# ZYNQ_Motherboard_final.net
KiCad netlist of a schematic drawn in Altium Designer
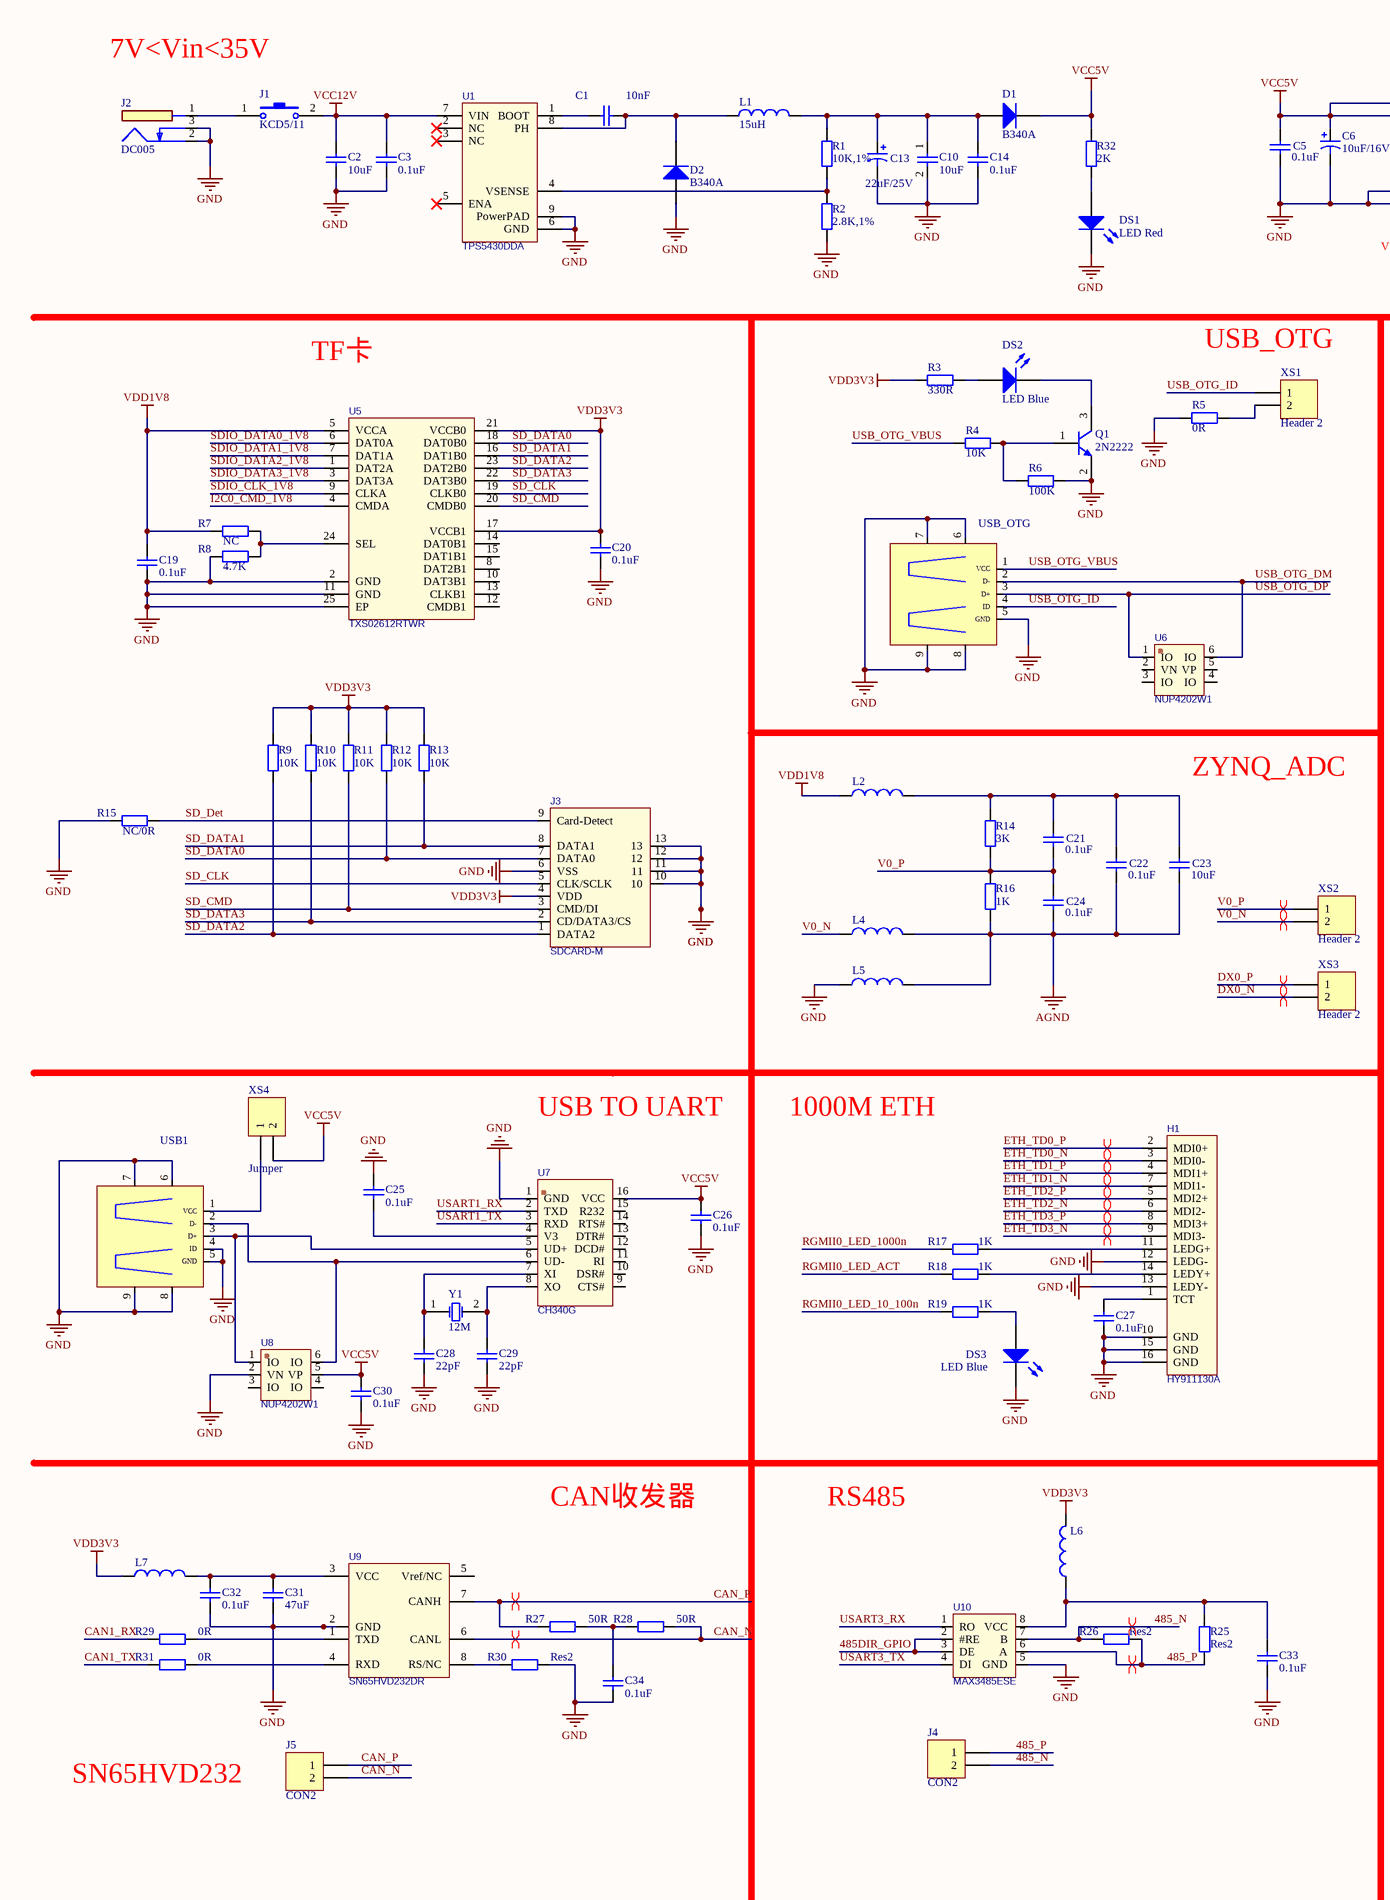
[diagram p0: ZYNQ_Motherboard_final.SchDoc, left]
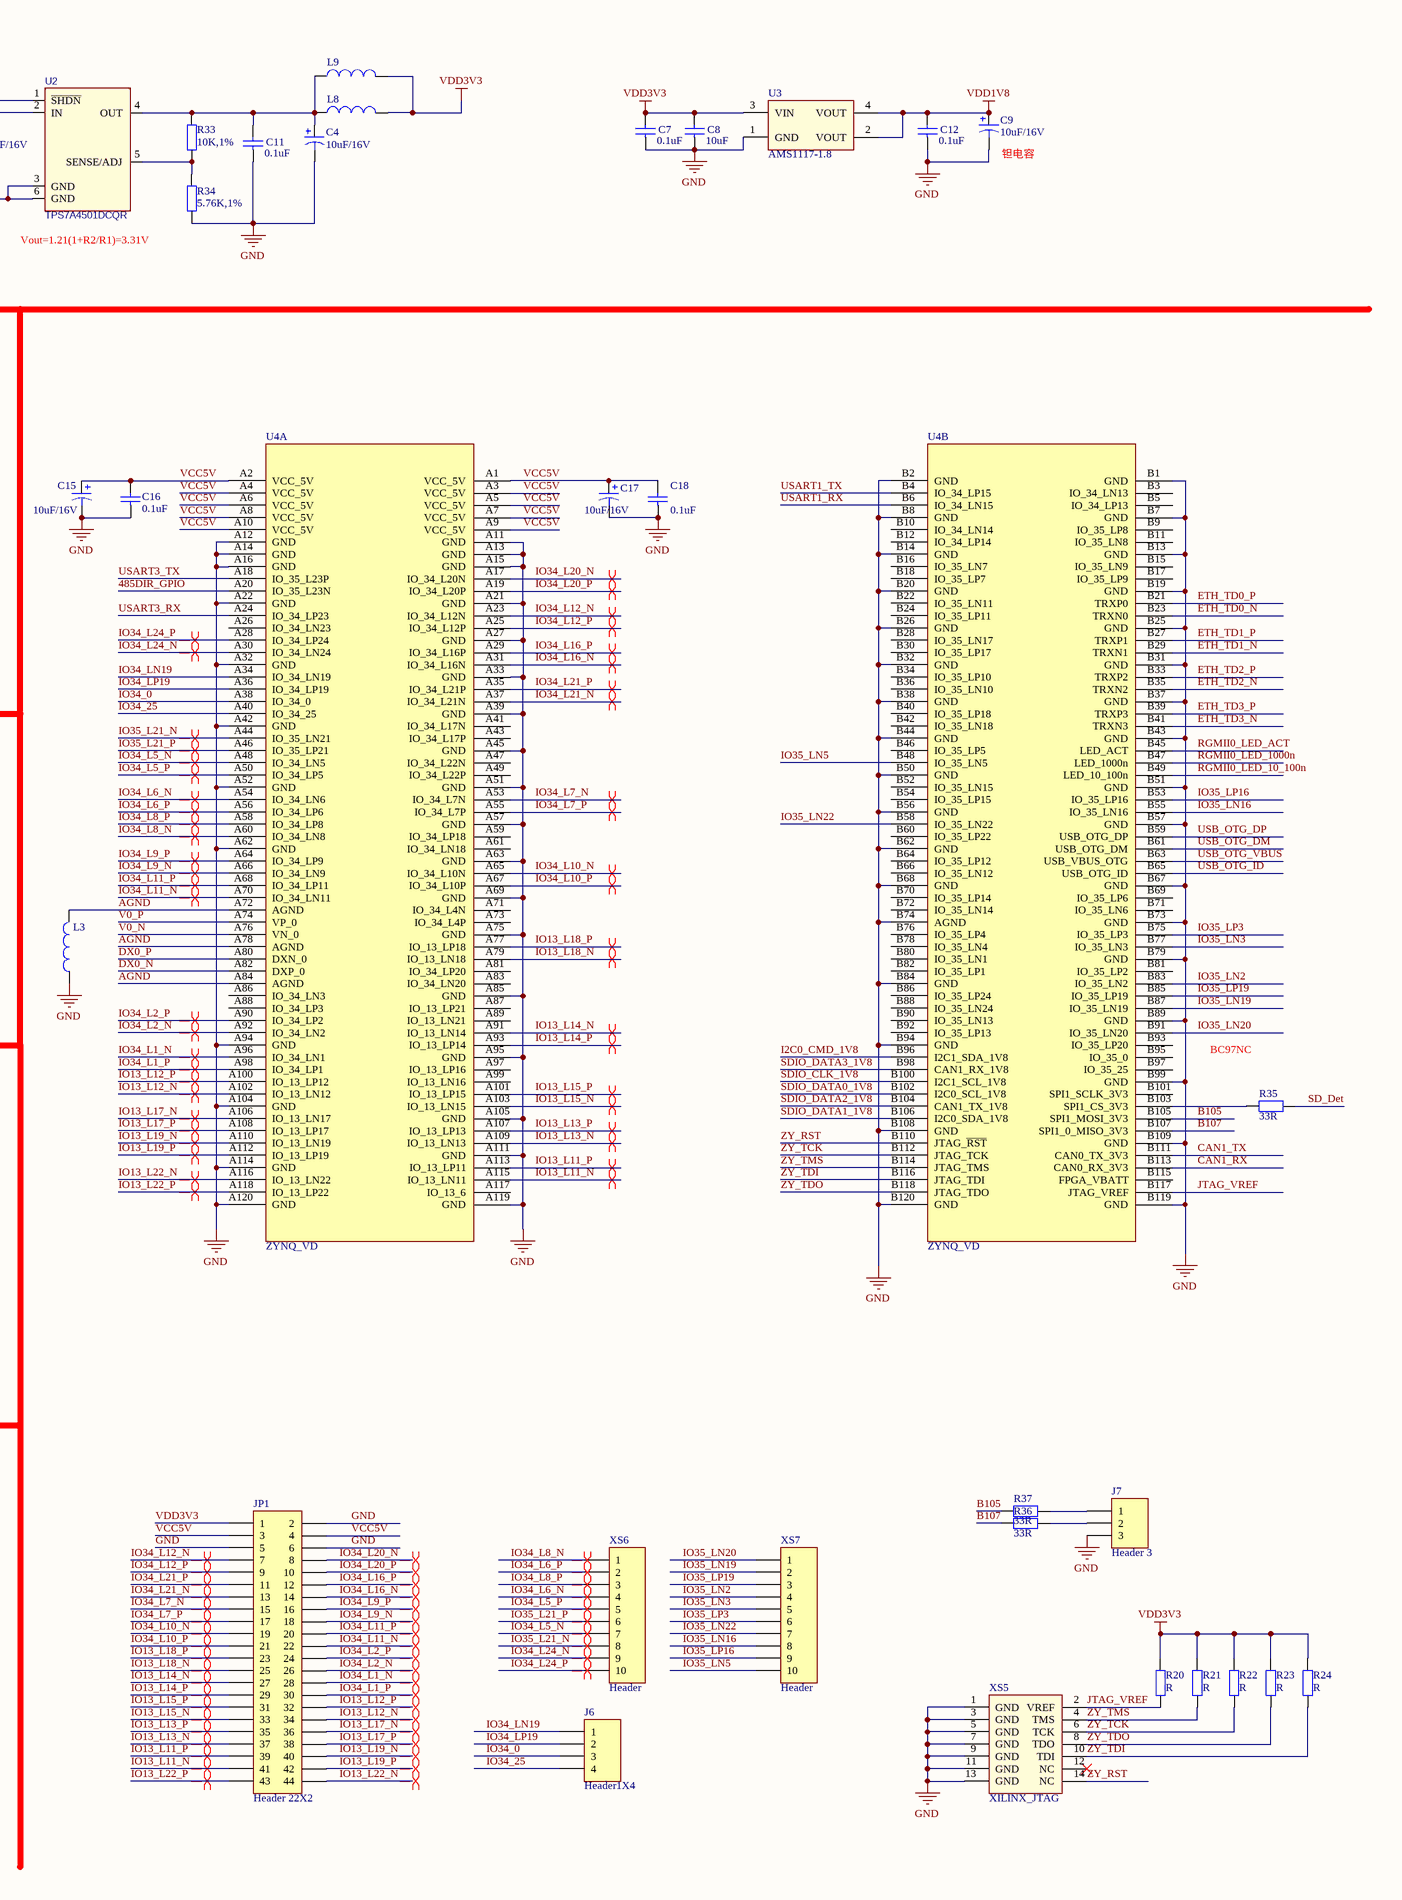
[diagram p1: ZYNQ_Motherboard_final.SchDoc, right]

(export (version "E")
  (design (tool "Eeschema 10.0.6"))
  (components
    (comp (ref "C1") (value "10nF") (footprint "0603") (libsource (lib "") (part "0603-CAP-50V 100±5%_1")))
    (comp (ref "C2") (value "10uF") (footprint "0805") (libsource (lib "") (part "0603-CAP-50V 100±5%_1")))
    (comp (ref "C3") (value "0.1uF") (footprint "0603") (libsource (lib "") (part "0603-CAP-50V 100±5%_1")))
    (comp (ref "C4")
      (value "10uF/16V")
      (footprint "shape_c")
      (description "Polarized Capacitor (Radial)")
      (fields (field (name "PUBLISHER") "Altium Limited"))
      (libsource (lib "") (part "Cap Pol1_1"))
    )
    (comp (ref "C5") (value "0.1uF") (footprint "0603") (libsource (lib "") (part "0603-CAP-50V 100±5%_1")))
    (comp (ref "C6")
      (value "10uF/16V")
      (footprint "shape_c")
      (description "Polarized Capacitor (Radial)")
      (fields (field (name "PUBLISHER") "Altium Limited"))
      (libsource (lib "") (part "Cap Pol1_1"))
    )
    (comp (ref "C7")
      (value "0.1uF")
      (footprint "0603")
      (libsource (lib "AJ-SCH_CAP") (part "0603-CAP-50V 100±5%"))
    )
    (comp (ref "C8")
      (value "10uF")
      (footprint "0805")
      (libsource (lib "AJ-SCH_CAP") (part "0603-CAP-50V 100±5%"))
    )
    (comp (ref "C9")
      (value "10uF/16V")
      (footprint "shape_c")
      (description "Polarized Capacitor (Radial)")
      (fields (field (name "PUBLISHER") "Altium Limited"))
      (libsource (lib "") (part "Cap Pol1_1"))
    )
    (comp (ref "C10") (value "10uF") (footprint "0805") (libsource (lib "") (part "0603-CAP-50V 100±5%_2")))
    (comp (ref "C11")
      (value "0.1uF")
      (footprint "0603")
      (libsource (lib "AJ-SCH_CAP") (part "0603-CAP-50V 100±5%"))
    )
    (comp (ref "C12")
      (value "0.1uF")
      (footprint "0603")
      (libsource (lib "AJ-SCH_CAP") (part "0603-CAP-50V 100±5%"))
    )
    (comp (ref "C13")
      (value "22uF/25V")
      (footprint "shape_c")
      (description "Polarized Capacitor (Radial)")
      (fields (field (name "PUBLISHER") "Altium Limited"))
      (libsource (lib "Miscellaneous Devices") (part "Cap Pol1"))
    )
    (comp (ref "C14") (value "0.1uF") (footprint "0603") (libsource (lib "") (part "0603-CAP-50V 100±5%_1")))
    (comp (ref "C15")
      (value "10uF/16V")
      (footprint "shape_c")
      (description "Polarized Capacitor (Radial)")
      (fields (field (name "PUBLISHER") "Altium Limited"))
      (libsource (lib "Miscellaneous Devices") (part "Cap Pol1"))
    )
    (comp (ref "C16") (value "0.1uF") (footprint "0603") (libsource (lib "") (part "0603-CAP-50V 100±5%_1")))
    (comp (ref "C17")
      (value "10uF/16V")
      (footprint "shape_c")
      (description "Polarized Capacitor (Radial)")
      (fields (field (name "PUBLISHER") "Altium Limited"))
      (libsource (lib "Miscellaneous Devices") (part "Cap Pol1"))
    )
    (comp (ref "C18") (value "0.1uF") (footprint "0603") (libsource (lib "") (part "0603-CAP-50V 100±5%_1")))
    (comp (ref "C19")
      (value "0.1uF")
      (footprint "0603")
      (libsource (lib "AJ-SCH_CAP") (part "0603-CAP-50V 100±5%"))
    )
    (comp (ref "C20")
      (value "0.1uF")
      (footprint "0603")
      (libsource (lib "AJ-SCH_CAP") (part "0603-CAP-50V 100±5%"))
    )
    (comp (ref "C21") (value "0.1uF") (footprint "0603") (libsource (lib "") (part "0603-CAP-50V 100±5%_1")))
    (comp (ref "C22") (value "0.1uF") (footprint "0603") (libsource (lib "") (part "0603-CAP-50V 100±5%_1")))
    (comp (ref "C23") (value "10uF") (footprint "0603") (libsource (lib "") (part "0603-CAP-50V 100±5%_1")))
    (comp (ref "C24") (value "0.1uF") (footprint "0603") (libsource (lib "") (part "0603-CAP-50V 100±5%_1")))
    (comp (ref "C25") (value "0.1uF") (footprint "0603") (libsource (lib "") (part "0603-CAP-50V 100±5%_1")))
    (comp (ref "C26")
      (value "0.1uF")
      (footprint "0603")
      (libsource (lib "AJ-SCH_CAP") (part "0603-CAP-50V 100±5%"))
    )
    (comp (ref "C27")
      (value "0.1uF")
      (footprint "0603")
      (libsource (lib "AJ-SCH_CAP") (part "0603-CAP-50V 100±5%"))
    )
    (comp (ref "C28") (value "22pF") (footprint "0603") (libsource (lib "") (part "0603-CAP-50V 100±5%_1")))
    (comp (ref "C29") (value "22pF") (footprint "0603") (libsource (lib "") (part "0603-CAP-50V 100±5%_1")))
    (comp (ref "C30") (value "0.1uF") (footprint "0603") (libsource (lib "") (part "0603-CAP-50V 100±5%_1")))
    (comp (ref "C31")
      (value "47uF")
      (footprint "0805")
      (libsource (lib "AJ-SCH_CAP") (part "0603-CAP-50V 100±5%"))
    )
    (comp (ref "C32")
      (value "0.1uF")
      (footprint "0603")
      (libsource (lib "AJ-SCH_CAP") (part "0603-CAP-50V 100±5%"))
    )
    (comp (ref "C33")
      (value "0.1uF")
      (footprint "0603")
      (libsource (lib "AJ-SCH_CAP") (part "0603-CAP-50V 100±5%"))
    )
    (comp (ref "C34")
      (value "0.1uF")
      (footprint "0603")
      (libsource (lib "AJ-SCH_CAP") (part "0603-CAP-50V 100±5%"))
    )
    (comp (ref "D1")
      (value "B340A")
      (footprint "SMA (DO-214AC)")
      (libsource (lib "AJ-SCH_Diode ") (part "SMD_整流二极管_FSL14"))
    )
    (comp (ref "D2")
      (value "B340A")
      (footprint "SMA (DO-214AC)")
      (libsource (lib "AJ-SCH_Diode ") (part "SMD_整流二极管_FSL14"))
    )
    (comp (ref "DS1")
      (value "LED Red")
      (footprint "SMDLED")
      (libsource (lib "AJ-SCH_Diode ") (part "0805_发光二极管_红色"))
    )
    (comp (ref "DS2")
      (value "LED Blue")
      (footprint "SMDLED")
      (libsource (lib "AJ-SCH_Diode ") (part "0805_发光二极管_红色"))
    )
    (comp (ref "DS3")
      (value "LED Blue")
      (footprint "SMDLED")
      (libsource (lib "AJ-SCH_Diode ") (part "0805_发光二极管_红色"))
    )
    (comp (ref "H1")
      (value "HY911130A")
      (footprint "RJ45_1000M")
      (fields (field (name "BOM_SUPPLIER PART") "C55679"))
      (libsource (lib "ZYNQ_Motherboard") (part "HY911130A"))
    )
    (comp (ref "J1")
      (value "KCD5/11")
      (footprint "KCD5/11")
      (description "Switch")
      (fields (field (name "PUBLISHER") "Altium Limited"))
      (libsource (lib "Miscellaneous Devices") (part "SW-PB"))
    )
    (comp (ref "J2")
      (value "DC005")
      (footprint "DC005")
      (description "Connector")
      (fields
        (field (name "MANUFACTURER_PART_NUMBER") "CON-SOCJ-2155")
        (field (name "MOUSER PART NUMBER") "992-CON-SOCJ-2155")
      )
      (libsource (lib "*") (part "CON-SOCJ-2155"))
    )
    (comp (ref "J3")
      (value "SDCARD-M")
      (footprint "SDCARD-M")
      (fields
        (field (name "BOM_SUPPLIER PART") "C202111")
        (field (name "BOM_MANUFACTURER PART") "DM3CS-SF")
        (field (name "CONTRIBUTOR") "LCSC")
      )
      (libsource (lib "ZYNQ_Motherboard") (part "DM3CS-SF"))
    )
    (comp (ref "J4")
      (value "CON2")
      (footprint "白色插座2")
      (description "Header, 2-Pin")
      (fields (field (name "PUBLISHER") "Altium Limited"))
      (libsource (lib "") (part "Header 2_2"))
    )
    (comp (ref "J5")
      (value "CON2")
      (footprint "白色插座2")
      (description "Header, 2-Pin")
      (fields (field (name "PUBLISHER") "Altium Limited"))
      (libsource (lib "") (part "Header 2_2"))
    )
    (comp (ref "J6")
      (value "Header1X4")
      (footprint "1X4_2.54")
      (description "Header, 4-Pin")
      (fields (field (name "PUBLISHER") "Altium Limited"))
      (libsource (lib "Miscellaneous Connectors") (part "Header 4"))
    )
    (comp (ref "J7")
      (value "Header 3")
      (footprint "HDR1X3")
      (description "Header, 3-Pin")
      (fields (field (name "PUBLISHER") "Altium Limited"))
      (libsource (lib "Miscellaneous Connectors") (part "Header 3"))
    )
    (comp (ref "JP1")
      (value "Header 22X2")
      (footprint "2x22_2.54")
      (description "Header, 22-Pin, Dual row")
      (fields (field (name "PUBLISHER") "Altium Limited"))
      (libsource (lib "Miscellaneous Connectors") (part "Header 22X2"))
    )
    (comp (ref "L1")
      (value "15uH")
      (footprint "L-SMD-12x12x10")
      (description "Inductor")
      (fields (field (name "PUBLISHER") "Altium Limited"))
      (libsource (lib "Miscellaneous Devices") (part "Inductor"))
    )
    (comp (ref "L2")
      (value "MPZ1608B471ATA00")
      (footprint "0603")
      (description "Inductor")
      (fields (field (name "PUBLISHER") "Altium Limited"))
      (libsource (lib "Miscellaneous Devices") (part "Inductor"))
    )
    (comp (ref "L3")
      (value "MPZ1608B471ATA00")
      (footprint "0603")
      (description "Inductor")
      (fields (field (name "PUBLISHER") "Altium Limited"))
      (libsource (lib "") (part "Inductor_1"))
    )
    (comp (ref "L4")
      (value "MPZ1608B471ATA00")
      (footprint "0603")
      (description "Inductor")
      (fields (field (name "PUBLISHER") "Altium Limited"))
      (libsource (lib "Miscellaneous Devices") (part "Inductor"))
    )
    (comp (ref "L5")
      (value "MPZ1608B471ATA00")
      (footprint "0603")
      (description "Inductor")
      (fields (field (name "PUBLISHER") "Altium Limited"))
      (libsource (lib "Miscellaneous Devices") (part "Inductor"))
    )
    (comp (ref "L6")
      (value "MPZ1608B471ATA00")
      (footprint "0603")
      (description "Inductor")
      (fields (field (name "PUBLISHER") "Altium Limited"))
      (libsource (lib "Miscellaneous Devices") (part "Inductor"))
    )
    (comp (ref "L7")
      (value "MPZ1608B471ATA00")
      (footprint "0603")
      (description "Inductor")
      (fields (field (name "PUBLISHER") "Altium Limited"))
      (libsource (lib "Miscellaneous Devices") (part "Inductor"))
    )
    (comp (ref "L8")
      (value "MPZ1608B471ATA00")
      (footprint "0603")
      (description "Inductor")
      (fields (field (name "PUBLISHER") "Altium Limited"))
      (libsource (lib "Miscellaneous Devices") (part "Inductor"))
    )
    (comp (ref "L9")
      (value "MPZ1608B471ATA00")
      (footprint "0603")
      (description "Inductor")
      (fields (field (name "PUBLISHER") "Altium Limited"))
      (libsource (lib "Miscellaneous Devices") (part "Inductor"))
    )
    (comp (ref "Q1")
      (value "2N2222")
      (footprint "SOT-23")
      (libsource (lib "AJ-SCH_Trans") (part "NPN_三极管_S9013 SOT-23"))
    )
    (comp (ref "R1")
      (value "10K,1%")
      (footprint "0603")
      (description "Resistor")
      (fields (field (name "PUBLISHER") "Altium Limited"))
      (libsource (lib "Miscellaneous Devices") (part "Res2"))
    )
    (comp (ref "R2")
      (value "2.8K,1%")
      (footprint "0603")
      (description "Resistor")
      (fields (field (name "PUBLISHER") "Altium Limited"))
      (libsource (lib "Miscellaneous Devices") (part "Res2"))
    )
    (comp (ref "R3")
      (value "330R")
      (footprint "0603")
      (description "Resistor")
      (fields (field (name "PUBLISHER") "Altium Limited"))
      (libsource (lib "") (part "Res2_1"))
    )
    (comp (ref "R4")
      (value "10K")
      (footprint "0603")
      (description "Resistor")
      (fields (field (name "PUBLISHER") "Altium Limited"))
      (libsource (lib "") (part "Res2_1"))
    )
    (comp (ref "R5")
      (value "0R")
      (footprint "0603")
      (description "Resistor")
      (fields (field (name "PUBLISHER") "Altium Limited"))
      (libsource (lib "") (part "Res2_1"))
    )
    (comp (ref "R6")
      (value "100K")
      (footprint "0603")
      (description "Resistor")
      (fields (field (name "PUBLISHER") "Altium Limited"))
      (libsource (lib "") (part "Res2_1"))
    )
    (comp (ref "R7")
      (value "NC")
      (footprint "0603")
      (description "Resistor")
      (fields (field (name "PUBLISHER") "Altium Limited"))
      (libsource (lib "") (part "Res2_1"))
    )
    (comp (ref "R8")
      (value "4.7K")
      (footprint "0603")
      (description "Resistor")
      (fields (field (name "PUBLISHER") "Altium Limited"))
      (libsource (lib "") (part "Res2_1"))
    )
    (comp (ref "R9")
      (value "10K")
      (footprint "0603")
      (description "Resistor")
      (fields (field (name "PUBLISHER") "Altium Limited"))
      (libsource (lib "") (part "Res2_3"))
    )
    (comp (ref "R10")
      (value "10K")
      (footprint "0603")
      (description "Resistor")
      (fields (field (name "PUBLISHER") "Altium Limited"))
      (libsource (lib "") (part "Res2_3"))
    )
    (comp (ref "R11")
      (value "10K")
      (footprint "0603")
      (description "Resistor")
      (fields (field (name "PUBLISHER") "Altium Limited"))
      (libsource (lib "") (part "Res2_3"))
    )
    (comp (ref "R12")
      (value "10K")
      (footprint "0603")
      (description "Resistor")
      (fields (field (name "PUBLISHER") "Altium Limited"))
      (libsource (lib "") (part "Res2_3"))
    )
    (comp (ref "R13")
      (value "10K")
      (footprint "0603")
      (description "Resistor")
      (fields (field (name "PUBLISHER") "Altium Limited"))
      (libsource (lib "") (part "Res2_3"))
    )
    (comp (ref "R14")
      (value "3K")
      (footprint "0603")
      (description "Resistor")
      (fields (field (name "PUBLISHER") "Altium Limited"))
      (libsource (lib "") (part "Res2_3"))
    )
    (comp (ref "R15")
      (value "NC/0R")
      (footprint "0603")
      (description "Resistor")
      (fields (field (name "PUBLISHER") "Altium Limited"))
      (libsource (lib "") (part "Res2_1"))
    )
    (comp (ref "R16")
      (value "1K")
      (footprint "0603")
      (description "Resistor")
      (fields (field (name "PUBLISHER") "Altium Limited"))
      (libsource (lib "") (part "Res2_3"))
    )
    (comp (ref "R17")
      (value "1K")
      (footprint "0603")
      (description "Resistor")
      (fields (field (name "PUBLISHER") "Altium Limited"))
      (libsource (lib "") (part "Res2_2"))
    )
    (comp (ref "R18")
      (value "1K")
      (footprint "0603")
      (description "Resistor")
      (fields (field (name "PUBLISHER") "Altium Limited"))
      (libsource (lib "") (part "Res2_2"))
    )
    (comp (ref "R19")
      (value "1K")
      (footprint "0603")
      (description "Resistor")
      (fields (field (name "PUBLISHER") "Altium Limited"))
      (libsource (lib "") (part "Res2_2"))
    )
    (comp (ref "R20")
      (value "R")
      (footprint "0603")
      (description "Resistor")
      (fields (field (name "PUBLISHER") "Altium Limited"))
      (libsource (lib "") (part "Res2_4"))
    )
    (comp (ref "R21")
      (value "R")
      (footprint "0603")
      (description "Resistor")
      (fields (field (name "PUBLISHER") "Altium Limited"))
      (libsource (lib "") (part "Res2_4"))
    )
    (comp (ref "R22")
      (value "R")
      (footprint "0603")
      (description "Resistor")
      (fields (field (name "PUBLISHER") "Altium Limited"))
      (libsource (lib "") (part "Res2_4"))
    )
    (comp (ref "R23")
      (value "R")
      (footprint "0603")
      (description "Resistor")
      (fields (field (name "PUBLISHER") "Altium Limited"))
      (libsource (lib "") (part "Res2_4"))
    )
    (comp (ref "R24")
      (value "R")
      (footprint "0603")
      (description "Resistor")
      (fields (field (name "PUBLISHER") "Altium Limited"))
      (libsource (lib "") (part "Res2_4"))
    )
    (comp (ref "R25")
      (value "Res2")
      (footprint "0603")
      (description "Resistor")
      (fields (field (name "PUBLISHER") "Altium Limited"))
      (libsource (lib "") (part "Res2_6"))
    )
    (comp (ref "R26")
      (value "Res2")
      (footprint "0603")
      (description "Resistor")
      (fields (field (name "PUBLISHER") "Altium Limited"))
      (libsource (lib "") (part "Res2_2"))
    )
    (comp (ref "R27")
      (value "50R")
      (footprint "0603")
      (description "Resistor")
      (fields (field (name "PUBLISHER") "Altium Limited"))
      (libsource (lib "") (part "Res2_2"))
    )
    (comp (ref "R28")
      (value "50R")
      (footprint "0603")
      (description "Resistor")
      (fields (field (name "PUBLISHER") "Altium Limited"))
      (libsource (lib "") (part "Res2_2"))
    )
    (comp (ref "R29")
      (value "0R")
      (footprint "0603")
      (description "Resistor")
      (fields (field (name "PUBLISHER") "Altium Limited"))
      (libsource (lib "") (part "Res2_2"))
    )
    (comp (ref "R30")
      (value "Res2")
      (footprint "0603")
      (description "Resistor")
      (fields (field (name "PUBLISHER") "Altium Limited"))
      (libsource (lib "") (part "Res2_7"))
    )
    (comp (ref "R31")
      (value "0R")
      (footprint "0603")
      (description "Resistor")
      (fields (field (name "PUBLISHER") "Altium Limited"))
      (libsource (lib "") (part "Res2_2"))
    )
    (comp (ref "R32")
      (value "2K")
      (footprint "0603")
      (description "Resistor")
      (fields (field (name "PUBLISHER") "Altium Limited"))
      (libsource (lib "Miscellaneous Devices") (part "Res2"))
    )
    (comp (ref "R33")
      (value "10K,1%")
      (footprint "0603")
      (description "Resistor")
      (fields (field (name "PUBLISHER") "Altium Limited"))
      (libsource (lib "Miscellaneous Devices") (part "Res2"))
    )
    (comp (ref "R34")
      (value "5.76K,1%")
      (footprint "0603")
      (description "Resistor")
      (fields (field (name "PUBLISHER") "Altium Limited"))
      (libsource (lib "Miscellaneous Devices") (part "Res2"))
    )
    (comp (ref "R35")
      (value "33R")
      (footprint "0603")
      (description "Resistor")
      (fields (field (name "PUBLISHER") "Altium Limited"))
      (libsource (lib "") (part "Res2_5"))
    )
    (comp (ref "R36")
      (value "33R")
      (footprint "0603")
      (description "Resistor")
      (fields (field (name "PUBLISHER") "Altium Limited"))
      (libsource (lib "") (part "Res2_2"))
    )
    (comp (ref "R37")
      (value "33R")
      (footprint "0603")
      (description "Resistor")
      (fields (field (name "PUBLISHER") "Altium Limited"))
      (libsource (lib "") (part "Res2_2"))
    )
    (comp (ref "U1")
      (value "TPS5430DDA")
      (footprint "SOIC8-PAD")
      (fields (field (name "BOM_MANUFACTURER PART") "TPS5430DDAR") (field (name "BOM_SUPPLIER PART") "C9864"))
      (libsource (lib "ZYNQ_Motherboard") (part "TPS5430DDAR"))
    )
    (comp (ref "U2")
      (value "TPS7A4501DCQR")
      (footprint "SOT223-6")
      (fields (field (name "BOM_SUPPLIER PART") "C840094") (field (name "CONTRIBUTOR") "LCSC"))
      (libsource (lib "ZYNQ_Motherboard") (part "TPS7A4501DCQR"))
    )
    (comp (ref "U3")
      (value "AMS1117-1.8")
      (footprint "SOT-223")
      (libsource (lib "ZYNQ_Motherboard") (part "AMS1117-1.8"))
    )
    (comp (ref "U4")
      (value "ZYNQ_VD")
      (footprint "ZYNQ_VD")
      (libsource (lib "ZYNQ_Motherboard") (part "ZYNQ"))
    )
    (comp (ref "U5")
      (value "TXS02612RTWR")
      (footprint "WQFN24_PAD")
      (fields (field (name "BOM_SUPPLIER PART") "C140276") (field (name "CONTRIBUTOR") "LCSC"))
      (libsource (lib "ZYNQ_Motherboard") (part "TXS02612RTWR"))
    )
    (comp (ref "U6")
      (value "NUP4202W1")
      (footprint "SOT-363")
      (fields
        (field (name "BOM_MANUFACTURER PART") "NUP4202W1T2G")
        (field (name "BOM_SUPPLIER PART") "C89319")
      )
      (libsource (lib "ZYNQ_Motherboard") (part "NUP4202W1T2G"))
    )
    (comp (ref "U7")
      (value "CH340G")
      (footprint "SOP16M")
      (fields (field (name "BOM_SUPPLIER PART") "C14267"))
      (libsource (lib "ZYNQ_Motherboard") (part "CH340G"))
    )
    (comp (ref "U8")
      (value "NUP4202W1")
      (footprint "SOT-363")
      (fields
        (field (name "BOM_MANUFACTURER PART") "NUP4202W1T2G")
        (field (name "BOM_SUPPLIER PART") "C89319")
      )
      (libsource (lib "ZYNQ_Motherboard") (part "NUP4202W1T2G"))
    )
    (comp (ref "U9")
      (value "SN65HVD232DR")
      (footprint "SOIC8")
      (fields (field (name "BOM_SUPPLIER PART") "C30530"))
      (libsource (lib "ZYNQ_Motherboard") (part "SN65HVD232DR"))
    )
    (comp (ref "U10")
      (value "MAX3485ESE")
      (footprint "SOP8")
      (fields
        (field (name "BOM_SUPPLIER PART") "C668204")
        (field (name "BOM_MANUFACTURER PART") "MAX3485ESA")
        (field (name "CONTRIBUTOR") "LCSC")
      )
      (libsource (lib "ZYNQ_Motherboard") (part "MAX3485ESE"))
    )
    (comp (ref "USB1")
      (value "USB")
      (footprint "USB/SM0.8-6H5")
      (libsource (lib "ZYNQ_Motherboard") (part "USB-micro"))
    )
    (comp (ref "USB_OTG")
      (value "USB")
      (footprint "USB/SM0.8-6H5")
      (libsource (lib "ZYNQ_Motherboard") (part "USB-micro"))
    )
    (comp (ref "XS1")
      (value "Header 2")
      (footprint "1X2_2.54")
      (description "Header, 2-Pin")
      (fields (field (name "PUBLISHER") "Altium Limited"))
      (libsource (lib "") (part "Header 2_1"))
    )
    (comp (ref "XS2")
      (value "Header 2")
      (footprint "1X2_2.54")
      (description "Header, 2-Pin")
      (fields (field (name "PUBLISHER") "Altium Limited"))
      (libsource (lib "") (part "Header 2_1"))
    )
    (comp (ref "XS3")
      (value "Header 2")
      (footprint "1X2_2.54")
      (description "Header, 2-Pin")
      (fields (field (name "PUBLISHER") "Altium Limited"))
      (libsource (lib "") (part "Header 2_1"))
    )
    (comp (ref "XS4")
      (value "Jumper")
      (footprint "1X2_2.54")
      (description "Header, 2-Pin")
      (fields (field (name "PUBLISHER") "Altium Limited"))
      (libsource (lib "Miscellaneous Connectors") (part "Header 2"))
    )
    (comp (ref "XS5")
      (value "XILINX_JTAG")
      (footprint "JTAG14-2.0")
      (libsource (lib "ZYNQ_Motherboard") (part "XILINX_JTAG"))
    )
    (comp (ref "XS6")
      (value "Header")
      (footprint "JTAG_10")
      (description "Header, 10-Pin")
      (fields (field (name "PUBLISHER") "Altium Limited"))
      (libsource (lib "Miscellaneous Connectors") (part "Header 10"))
    )
    (comp (ref "XS7")
      (value "Header")
      (footprint "1x9_2.0")
      (description "Header, 10-Pin")
      (fields (field (name "PUBLISHER") "Altium Limited"))
      (libsource (lib "Miscellaneous Connectors") (part "Header 10"))
    )
    (comp (ref "Y1") (value "12M") (footprint "晶振") (libsource (lib "AJ-SCH_SW") (part "晶振(DIP 3)_4MHz")))
  )
  (nets
    (net (code "1") (name "/485DIR_GPIO") (class "Default")
      (node (ref "U10") (pin "2") (pinfunction "#RE_2") (pintype "passive"))
      (node (ref "U10") (pin "3") (pinfunction "DE_3") (pintype "passive"))
      (node (ref "U4") (pin "A20") (pinfunction "IO_35_L23N_A20") (pintype "passive"))
    )
    (net (code "2") (name "/485_N") (class "Default")
      (node (ref "J4") (pin "2") (pinfunction "2_2") (pintype "passive"))
      (node (ref "R26") (pin "1") (pinfunction "1_1") (pintype "passive"))
      (node (ref "U10") (pin "7") (pinfunction "B_7") (pintype "passive"))
    )
    (net (code "3") (name "/485_P") (class "Default")
      (node (ref "J4") (pin "1") (pinfunction "1_1") (pintype "passive"))
      (node (ref "R25") (pin "1") (pinfunction "1_1") (pintype "passive"))
      (node (ref "R26") (pin "2") (pinfunction "2_2") (pintype "passive"))
      (node (ref "U10") (pin "6") (pinfunction "A_6") (pintype "passive"))
    )
    (net (code "4") (name "/B105") (class "Default")
      (node (ref "R37") (pin "1") (pinfunction "1_1") (pintype "passive"))
      (node (ref "U4") (pin "B105") (pinfunction "SPI1_MOSI_3V3_B105") (pintype "passive"))
    )
    (net (code "5") (name "/B107") (class "Default")
      (node (ref "R36") (pin "1") (pinfunction "1_1") (pintype "passive"))
      (node (ref "U4") (pin "B107") (pinfunction "SPI1_0_MISO_3V3_B107") (pintype "passive"))
    )
    (net (code "6") (name "/CAN1_RX") (class "Default")
      (node (ref "R29") (pin "1") (pinfunction "1_1") (pintype "passive"))
      (node (ref "U4") (pin "B113") (pinfunction "CAN0_RX_3V3_B113") (pintype "passive"))
    )
    (net (code "7") (name "/CAN1_TX") (class "Default")
      (node (ref "R31") (pin "1") (pinfunction "1_1") (pintype "passive"))
      (node (ref "U4") (pin "B111") (pinfunction "CAN0_TX_3V3_B111") (pintype "passive"))
    )
    (net (code "8") (name "/CAN_N") (class "Default")
      (node (ref "J5") (pin "2") (pinfunction "2_2") (pintype "passive"))
      (node (ref "R28") (pin "2") (pinfunction "2_2") (pintype "passive"))
      (node (ref "U9") (pin "6") (pinfunction "CANL_6") (pintype "passive"))
    )
    (net (code "9") (name "/CAN_P") (class "Default")
      (node (ref "J5") (pin "1") (pinfunction "1_1") (pintype "passive"))
      (node (ref "R27") (pin "1") (pinfunction "1_1") (pintype "passive"))
      (node (ref "U9") (pin "7") (pinfunction "CANH_7") (pintype "passive"))
    )
    (net (code "10") (name "/DX0_N") (class "Default")
      (node (ref "U4") (pin "A82") (pinfunction "DXP_0_A82") (pintype "passive"))
      (node (ref "XS3") (pin "2") (pinfunction "2_2") (pintype "passive"))
    )
    (net (code "11") (name "/DX0_P") (class "Default")
      (node (ref "U4") (pin "A80") (pinfunction "DXN_0_A80") (pintype "passive"))
      (node (ref "XS3") (pin "1") (pinfunction "1_1") (pintype "passive"))
    )
    (net (code "12") (name "/ETH_TD0_N") (class "Default")
      (node (ref "H1") (pin "3") (pinfunction "MDI0-_3") (pintype "passive"))
      (node (ref "U4") (pin "B23") (pinfunction "TRXN0_B23") (pintype "passive"))
    )
    (net (code "13") (name "/ETH_TD0_P") (class "Default")
      (node (ref "H1") (pin "2") (pinfunction "MDI0+_2") (pintype "passive"))
      (node (ref "U4") (pin "B21") (pinfunction "TRXP0_B21") (pintype "passive"))
    )
    (net (code "14") (name "/ETH_TD1_N") (class "Default")
      (node (ref "H1") (pin "7") (pinfunction "MDI1-_7") (pintype "passive"))
      (node (ref "U4") (pin "B29") (pinfunction "TRXN1_B29") (pintype "passive"))
    )
    (net (code "15") (name "/ETH_TD1_P") (class "Default")
      (node (ref "H1") (pin "4") (pinfunction "MDI1+_4") (pintype "passive"))
      (node (ref "U4") (pin "B27") (pinfunction "TRXP1_B27") (pintype "passive"))
    )
    (net (code "16") (name "/ETH_TD2_N") (class "Default")
      (node (ref "H1") (pin "6") (pinfunction "MDI2-_6") (pintype "passive"))
      (node (ref "U4") (pin "B35") (pinfunction "TRXN2_B35") (pintype "passive"))
    )
    (net (code "17") (name "/ETH_TD2_P") (class "Default")
      (node (ref "H1") (pin "5") (pinfunction "MDI2+_5") (pintype "passive"))
      (node (ref "U4") (pin "B33") (pinfunction "TRXP2_B33") (pintype "passive"))
    )
    (net (code "18") (name "/ETH_TD3_N") (class "Default")
      (node (ref "H1") (pin "9") (pinfunction "MDI3-_9") (pintype "passive"))
      (node (ref "U4") (pin "B41") (pinfunction "TRXN3_B41") (pintype "passive"))
    )
    (net (code "19") (name "/ETH_TD3_P") (class "Default")
      (node (ref "H1") (pin "8") (pinfunction "MDI3+_8") (pintype "passive"))
      (node (ref "U4") (pin "B39") (pinfunction "TRXP3_B39") (pintype "passive"))
    )
    (net (code "20") (name "/I2C0_CMD_1V8") (class "Default")
      (node (ref "U4") (pin "B96") (pinfunction "I2C1_SDA_1V8_B96") (pintype "passive"))
      (node (ref "U5") (pin "4") (pinfunction "CMDA_4") (pintype "passive"))
    )
    (net (code "21") (name "/IO13_L11_N") (class "Default")
      (node (ref "JP1") (pin "41") (pinfunction "41_41") (pintype "passive"))
      (node (ref "U4") (pin "A115") (pinfunction "IO_13_LN11_A115") (pintype "passive"))
    )
    (net (code "22") (name "/IO13_L11_P") (class "Default")
      (node (ref "JP1") (pin "39") (pinfunction "39_39") (pintype "passive"))
      (node (ref "U4") (pin "A113") (pinfunction "IO_13_LP11_A113") (pintype "passive"))
    )
    (net (code "23") (name "/IO13_L12_N") (class "Default")
      (node (ref "JP1") (pin "34") (pinfunction "34_34") (pintype "passive"))
      (node (ref "U4") (pin "A102") (pinfunction "IO_13_LN12_A102") (pintype "passive"))
    )
    (net (code "24") (name "/IO13_L12_P") (class "Default")
      (node (ref "JP1") (pin "32") (pinfunction "32_32") (pintype "passive"))
      (node (ref "U4") (pin "A100") (pinfunction "IO_13_LP12_A100") (pintype "passive"))
    )
    (net (code "25") (name "/IO13_L13_N") (class "Default")
      (node (ref "JP1") (pin "37") (pinfunction "37_37") (pintype "passive"))
      (node (ref "U4") (pin "A109") (pinfunction "IO_13_LN13_A109") (pintype "passive"))
    )
    (net (code "26") (name "/IO13_L13_P") (class "Default")
      (node (ref "JP1") (pin "35") (pinfunction "35_35") (pintype "passive"))
      (node (ref "U4") (pin "A107") (pinfunction "IO_13_LP13_A107") (pintype "passive"))
    )
    (net (code "27") (name "/IO13_L14_N") (class "Default")
      (node (ref "JP1") (pin "27") (pinfunction "27_27") (pintype "passive"))
      (node (ref "U4") (pin "A91") (pinfunction "IO_13_LN14_A91") (pintype "passive"))
    )
    (net (code "28") (name "/IO13_L14_P") (class "Default")
      (node (ref "JP1") (pin "29") (pinfunction "29_29") (pintype "passive"))
      (node (ref "U4") (pin "A93") (pinfunction "IO_13_LP14_A93") (pintype "passive"))
    )
    (net (code "29") (name "/IO13_L15_N") (class "Default")
      (node (ref "JP1") (pin "33") (pinfunction "33_33") (pintype "passive"))
      (node (ref "U4") (pin "A103") (pinfunction "IO_13_LN15_A103") (pintype "passive"))
    )
    (net (code "30") (name "/IO13_L15_P") (class "Default")
      (node (ref "JP1") (pin "31") (pinfunction "31_31") (pintype "passive"))
      (node (ref "U4") (pin "A101") (pinfunction "IO_13_LP15_A101") (pintype "passive"))
    )
    (net (code "31") (name "/IO13_L17_N") (class "Default")
      (node (ref "JP1") (pin "36") (pinfunction "36_36") (pintype "passive"))
      (node (ref "U4") (pin "A106") (pinfunction "IO_13_LN17_A106") (pintype "passive"))
    )
    (net (code "32") (name "/IO13_L17_P") (class "Default")
      (node (ref "JP1") (pin "38") (pinfunction "38_38") (pintype "passive"))
      (node (ref "U4") (pin "A108") (pinfunction "IO_13_LP17_A108") (pintype "passive"))
    )
    (net (code "33") (name "/IO13_L18_N") (class "Default")
      (node (ref "JP1") (pin "25") (pinfunction "25_25") (pintype "passive"))
      (node (ref "U4") (pin "A79") (pinfunction "IO_13_LN18_A79") (pintype "passive"))
    )
    (net (code "34") (name "/IO13_L18_P") (class "Default")
      (node (ref "JP1") (pin "23") (pinfunction "23_23") (pintype "passive"))
      (node (ref "U4") (pin "A77") (pinfunction "IO_13_LP18_A77") (pintype "passive"))
    )
    (net (code "35") (name "/IO13_L19_N") (class "Default")
      (node (ref "JP1") (pin "40") (pinfunction "40_40") (pintype "passive"))
      (node (ref "U4") (pin "A110") (pinfunction "IO_13_LN19_A110") (pintype "passive"))
    )
    (net (code "36") (name "/IO13_L19_P") (class "Default")
      (node (ref "JP1") (pin "42") (pinfunction "42_42") (pintype "passive"))
      (node (ref "U4") (pin "A112") (pinfunction "IO_13_LP19_A112") (pintype "passive"))
    )
    (net (code "37") (name "/IO13_L22_N") (class "Default")
      (node (ref "JP1") (pin "44") (pinfunction "44_44") (pintype "passive"))
      (node (ref "U4") (pin "A116") (pinfunction "IO_13_LN22_A116") (pintype "passive"))
    )
    (net (code "38") (name "/IO13_L22_P") (class "Default")
      (node (ref "JP1") (pin "43") (pinfunction "43_43") (pintype "passive"))
      (node (ref "U4") (pin "A118") (pinfunction "IO_13_LP22_A118") (pintype "passive"))
    )
    (net (code "39") (name "/IO34_0") (class "Default")
      (node (ref "J6") (pin "3") (pinfunction "3_3") (pintype "passive"))
      (node (ref "U4") (pin "A38") (pinfunction "IO_34_0_A38") (pintype "passive"))
    )
    (net (code "40") (name "/IO34_25") (class "Default")
      (node (ref "J6") (pin "4") (pinfunction "4_4") (pintype "passive"))
      (node (ref "U4") (pin "A40") (pinfunction "IO_34_25_A40") (pintype "passive"))
    )
    (net (code "41") (name "/IO34_L1_N") (class "Default")
      (node (ref "JP1") (pin "28") (pinfunction "28_28") (pintype "passive"))
      (node (ref "U4") (pin "A96") (pinfunction "IO_34_LN1_A96") (pintype "passive"))
    )
    (net (code "42") (name "/IO34_L1_P") (class "Default")
      (node (ref "JP1") (pin "30") (pinfunction "30_30") (pintype "passive"))
      (node (ref "U4") (pin "A98") (pinfunction "IO_34_LP1_A98") (pintype "passive"))
    )
    (net (code "43") (name "/IO34_L2_N") (class "Default")
      (node (ref "JP1") (pin "26") (pinfunction "26_26") (pintype "passive"))
      (node (ref "U4") (pin "A92") (pinfunction "IO_34_LN2_A92") (pintype "passive"))
    )
    (net (code "44") (name "/IO34_L2_P") (class "Default")
      (node (ref "JP1") (pin "24") (pinfunction "24_24") (pintype "passive"))
      (node (ref "U4") (pin "A90") (pinfunction "IO_34_LP2_A90") (pintype "passive"))
    )
    (net (code "45") (name "/IO34_L5_N") (class "Default")
      (node (ref "U4") (pin "A48") (pinfunction "IO_34_LN5_A48") (pintype "passive"))
      (node (ref "XS6") (pin "7") (pinfunction "7_7") (pintype "passive"))
    )
    (net (code "46") (name "/IO34_L5_P") (class "Default")
      (node (ref "U4") (pin "A50") (pinfunction "IO_34_LP5_A50") (pintype "passive"))
      (node (ref "XS6") (pin "5") (pinfunction "5_5") (pintype "passive"))
    )
    (net (code "47") (name "/IO34_L6_N") (class "Default")
      (node (ref "U4") (pin "A54") (pinfunction "IO_34_LN6_A54") (pintype "passive"))
      (node (ref "XS6") (pin "4") (pinfunction "4_4") (pintype "passive"))
    )
    (net (code "48") (name "/IO34_L6_P") (class "Default")
      (node (ref "U4") (pin "A56") (pinfunction "IO_34_LP6_A56") (pintype "passive"))
      (node (ref "XS6") (pin "2") (pinfunction "2_2") (pintype "passive"))
    )
    (net (code "49") (name "/IO34_L7_N") (class "Default")
      (node (ref "JP1") (pin "15") (pinfunction "15_15") (pintype "passive"))
      (node (ref "U4") (pin "A53") (pinfunction "IO_34_L7N_A53") (pintype "passive"))
    )
    (net (code "50") (name "/IO34_L7_P") (class "Default")
      (node (ref "JP1") (pin "17") (pinfunction "17_17") (pintype "passive"))
      (node (ref "U4") (pin "A55") (pinfunction "IO_34_L7P_A55") (pintype "passive"))
    )
    (net (code "51") (name "/IO34_L8_N") (class "Default")
      (node (ref "U4") (pin "A60") (pinfunction "IO_34_LN8_A60") (pintype "passive"))
      (node (ref "XS6") (pin "1") (pinfunction "1_1") (pintype "passive"))
    )
    (net (code "52") (name "/IO34_L8_P") (class "Default")
      (node (ref "U4") (pin "A58") (pinfunction "IO_34_LP8_A58") (pintype "passive"))
      (node (ref "XS6") (pin "3") (pinfunction "3_3") (pintype "passive"))
    )
    (net (code "53") (name "/IO34_L9_N") (class "Default")
      (node (ref "JP1") (pin "18") (pinfunction "18_18") (pintype "passive"))
      (node (ref "U4") (pin "A66") (pinfunction "IO_34_LN9_A66") (pintype "passive"))
    )
    (net (code "54") (name "/IO34_L9_P") (class "Default")
      (node (ref "JP1") (pin "16") (pinfunction "16_16") (pintype "passive"))
      (node (ref "U4") (pin "A64") (pinfunction "IO_34_LP9_A64") (pintype "passive"))
    )
    (net (code "55") (name "/IO34_L10_N") (class "Default")
      (node (ref "JP1") (pin "19") (pinfunction "19_19") (pintype "passive"))
      (node (ref "U4") (pin "A65") (pinfunction "IO_34_L10N_A65") (pintype "passive"))
    )
    (net (code "56") (name "/IO34_L10_P") (class "Default")
      (node (ref "JP1") (pin "21") (pinfunction "21_21") (pintype "passive"))
      (node (ref "U4") (pin "A67") (pinfunction "IO_34_L10P_A67") (pintype "passive"))
    )
    (net (code "57") (name "/IO34_L11_N") (class "Default")
      (node (ref "JP1") (pin "22") (pinfunction "22_22") (pintype "passive"))
      (node (ref "U4") (pin "A70") (pinfunction "IO_34_LN11_A70") (pintype "passive"))
    )
    (net (code "58") (name "/IO34_L11_P") (class "Default")
      (node (ref "JP1") (pin "20") (pinfunction "20_20") (pintype "passive"))
      (node (ref "U4") (pin "A68") (pinfunction "IO_34_LP11_A68") (pintype "passive"))
    )
    (net (code "59") (name "/IO34_L12_N") (class "Default")
      (node (ref "JP1") (pin "7") (pinfunction "7_7") (pintype "passive"))
      (node (ref "U4") (pin "A23") (pinfunction "IO_34_L12N_A23") (pintype "passive"))
    )
    (net (code "60") (name "/IO34_L12_P") (class "Default")
      (node (ref "JP1") (pin "9") (pinfunction "9_9") (pintype "passive"))
      (node (ref "U4") (pin "A25") (pinfunction "IO_34_L12P_A25") (pintype "passive"))
    )
    (net (code "61") (name "/IO34_L16_N") (class "Default")
      (node (ref "JP1") (pin "14") (pinfunction "14_14") (pintype "passive"))
      (node (ref "U4") (pin "A31") (pinfunction "IO_34_L16N_A31") (pintype "passive"))
    )
    (net (code "62") (name "/IO34_L16_P") (class "Default")
      (node (ref "JP1") (pin "12") (pinfunction "12_12") (pintype "passive"))
      (node (ref "U4") (pin "A29") (pinfunction "IO_34_L16P_A29") (pintype "passive"))
    )
    (net (code "63") (name "/IO34_L20_N") (class "Default")
      (node (ref "JP1") (pin "8") (pinfunction "8_8") (pintype "passive"))
      (node (ref "U4") (pin "A17") (pinfunction "IO_34_L20N_A17") (pintype "passive"))
    )
    (net (code "64") (name "/IO34_L20_P") (class "Default")
      (node (ref "JP1") (pin "10") (pinfunction "10_10") (pintype "passive"))
      (node (ref "U4") (pin "A19") (pinfunction "IO_34_L20P_A19") (pintype "passive"))
    )
    (net (code "65") (name "/IO34_L21_N") (class "Default")
      (node (ref "JP1") (pin "13") (pinfunction "13_13") (pintype "passive"))
      (node (ref "U4") (pin "A37") (pinfunction "IO_34_L21N_A37") (pintype "passive"))
    )
    (net (code "66") (name "/IO34_L21_P") (class "Default")
      (node (ref "JP1") (pin "11") (pinfunction "11_11") (pintype "passive"))
      (node (ref "U4") (pin "A35") (pinfunction "IO_34_L21P_A35") (pintype "passive"))
    )
    (net (code "67") (name "/IO34_L24_N") (class "Default")
      (node (ref "U4") (pin "A30") (pinfunction "IO_34_LN24_A30") (pintype "passive"))
      (node (ref "XS6") (pin "9") (pinfunction "9_9") (pintype "passive"))
    )
    (net (code "68") (name "/IO34_L24_P") (class "Default")
      (node (ref "U4") (pin "A28") (pinfunction "IO_34_LP24_A28") (pintype "passive"))
      (node (ref "XS6") (pin "10") (pinfunction "10_10") (pintype "passive"))
    )
    (net (code "69") (name "/IO34_LN19") (class "Default")
      (node (ref "J6") (pin "1") (pinfunction "1_1") (pintype "passive"))
      (node (ref "U4") (pin "A34") (pinfunction "IO_34_LN19_A34") (pintype "passive"))
    )
    (net (code "70") (name "/IO34_LP19") (class "Default")
      (node (ref "J6") (pin "2") (pinfunction "2_2") (pintype "passive"))
      (node (ref "U4") (pin "A36") (pinfunction "IO_34_LP19_A36") (pintype "passive"))
    )
    (net (code "71") (name "/IO35_L21_N") (class "Default")
      (node (ref "U4") (pin "A44") (pinfunction "IO_35_LN21_A44") (pintype "passive"))
      (node (ref "XS6") (pin "8") (pinfunction "8_8") (pintype "passive"))
    )
    (net (code "72") (name "/IO35_L21_P") (class "Default")
      (node (ref "U4") (pin "A46") (pinfunction "IO_35_LP21_A46") (pintype "passive"))
      (node (ref "XS6") (pin "6") (pinfunction "6_6") (pintype "passive"))
    )
    (net (code "73") (name "/IO35_LN2") (class "Default")
      (node (ref "U4") (pin "B83") (pinfunction "IO_35_LN2_B83") (pintype "passive"))
      (node (ref "XS7") (pin "4") (pinfunction "4_4") (pintype "passive"))
    )
    (net (code "74") (name "/IO35_LN3") (class "Default")
      (node (ref "U4") (pin "B77") (pinfunction "IO_35_LN3_B77") (pintype "passive"))
      (node (ref "XS7") (pin "5") (pinfunction "5_5") (pintype "passive"))
    )
    (net (code "75") (name "/IO35_LN5") (class "Default")
      (node (ref "U4") (pin "B48") (pinfunction "IO_35_LN5_B48") (pintype "passive"))
      (node (ref "XS7") (pin "10") (pinfunction "10_10") (pintype "passive"))
    )
    (net (code "76") (name "/IO35_LN16") (class "Default")
      (node (ref "U4") (pin "B55") (pinfunction "IO_35_LN16_B55") (pintype "passive"))
      (node (ref "XS7") (pin "8") (pinfunction "8_8") (pintype "passive"))
    )
    (net (code "77") (name "/IO35_LN19") (class "Default")
      (node (ref "U4") (pin "B87") (pinfunction "IO_35_LN19_B87") (pintype "passive"))
      (node (ref "XS7") (pin "2") (pinfunction "2_2") (pintype "passive"))
    )
    (net (code "78") (name "/IO35_LN20") (class "Default")
      (node (ref "U4") (pin "B91") (pinfunction "IO_35_LN20_B91") (pintype "passive"))
      (node (ref "XS7") (pin "1") (pinfunction "1_1") (pintype "passive"))
    )
    (net (code "79") (name "/IO35_LN22") (class "Default")
      (node (ref "U4") (pin "B58") (pinfunction "IO_35_LN22_B58") (pintype "passive"))
      (node (ref "XS7") (pin "7") (pinfunction "7_7") (pintype "passive"))
    )
    (net (code "80") (name "/IO35_LP3") (class "Default")
      (node (ref "U4") (pin "B75") (pinfunction "IO_35_LP3_B75") (pintype "passive"))
      (node (ref "XS7") (pin "6") (pinfunction "6_6") (pintype "passive"))
    )
    (net (code "81") (name "/IO35_LP16") (class "Default")
      (node (ref "U4") (pin "B53") (pinfunction "IO_35_LP16_B53") (pintype "passive"))
      (node (ref "XS7") (pin "9") (pinfunction "9_9") (pintype "passive"))
    )
    (net (code "82") (name "/IO35_LP19") (class "Default")
      (node (ref "U4") (pin "B85") (pinfunction "IO_35_LP19_B85") (pintype "passive"))
      (node (ref "XS7") (pin "3") (pinfunction "3_3") (pintype "passive"))
    )
    (net (code "83") (name "/JTAG_VREF") (class "Default")
      (node (ref "R20") (pin "1") (pinfunction "1_1") (pintype "passive"))
      (node (ref "U4") (pin "B117") (pinfunction "JTAG_VREF_B117") (pintype "passive"))
      (node (ref "XS5") (pin "2") (pinfunction "VREF_2") (pintype "passive"))
    )
    (net (code "84") (name "/RGMII0_LED_10_100n") (class "Default")
      (node (ref "R19") (pin "1") (pinfunction "1_1") (pintype "passive"))
      (node (ref "U4") (pin "B49") (pinfunction "LED_10_100n_B49") (pintype "passive"))
    )
    (net (code "85") (name "/RGMII0_LED_1000n") (class "Default")
      (node (ref "R17") (pin "1") (pinfunction "1_1") (pintype "passive"))
      (node (ref "U4") (pin "B47") (pinfunction "LED_1000n_B47") (pintype "passive"))
    )
    (net (code "86") (name "/RGMII0_LED_ACT") (class "Default")
      (node (ref "R18") (pin "1") (pinfunction "1_1") (pintype "passive"))
      (node (ref "U4") (pin "B45") (pinfunction "LED_ACT_B45") (pintype "passive"))
    )
    (net (code "87") (name "/SDIO_CLK_1V8") (class "Default")
      (node (ref "U4") (pin "B100") (pinfunction "I2C1_SCL_1V8_B100") (pintype "passive"))
      (node (ref "U5") (pin "9") (pinfunction "CLKA_9") (pintype "passive"))
    )
    (net (code "88") (name "/SDIO_DATA0_1V8") (class "Default")
      (node (ref "U4") (pin "B102") (pinfunction "I2C0_SCL_1V8_B102") (pintype "passive"))
      (node (ref "U5") (pin "6") (pinfunction "DAT0A_6") (pintype "passive"))
    )
    (net (code "89") (name "/SDIO_DATA1_1V8") (class "Default")
      (node (ref "U4") (pin "B106") (pinfunction "I2C0_SDA_1V8_B106") (pintype "passive"))
      (node (ref "U5") (pin "7") (pinfunction "DAT1A_7") (pintype "passive"))
    )
    (net (code "90") (name "/SDIO_DATA2_1V8") (class "Default")
      (node (ref "U4") (pin "B104") (pinfunction "CAN1_TX_1V8_B104") (pintype "passive"))
      (node (ref "U5") (pin "1") (pinfunction "DAT2A_1") (pintype "passive"))
    )
    (net (code "91") (name "/SDIO_DATA3_1V8") (class "Default")
      (node (ref "U4") (pin "B98") (pinfunction "CAN1_RX_1V8_B98") (pintype "passive"))
      (node (ref "U5") (pin "3") (pinfunction "DAT3A_3") (pintype "passive"))
    )
    (net (code "92") (name "/SD_CLK") (class "Default")
      (node (ref "J3") (pin "5") (pinfunction "CLK/SCLK_5") (pintype "passive"))
      (node (ref "U5") (pin "19") (pinfunction "CLKB0_19") (pintype "passive"))
    )
    (net (code "93") (name "/SD_CMD") (class "Default")
      (node (ref "J3") (pin "3") (pinfunction "CMD/DI_3") (pintype "passive"))
      (node (ref "R11") (pin "2") (pinfunction "2_2") (pintype "passive"))
      (node (ref "U5") (pin "20") (pinfunction "CMDB0_20") (pintype "passive"))
    )
    (net (code "94") (name "/SD_DATA0") (class "Default")
      (node (ref "J3") (pin "7") (pinfunction "DATA0_7") (pintype "passive"))
      (node (ref "R12") (pin "2") (pinfunction "2_2") (pintype "passive"))
      (node (ref "U5") (pin "18") (pinfunction "DAT0B0_18") (pintype "passive"))
    )
    (net (code "95") (name "/SD_DATA1") (class "Default")
      (node (ref "J3") (pin "8") (pinfunction "DATA1_8") (pintype "passive"))
      (node (ref "R13") (pin "2") (pinfunction "2_2") (pintype "passive"))
      (node (ref "U5") (pin "16") (pinfunction "DAT1B0_16") (pintype "passive"))
    )
    (net (code "96") (name "/SD_DATA2") (class "Default")
      (node (ref "J3") (pin "1") (pinfunction "DATA2_1") (pintype "passive"))
      (node (ref "R9") (pin "2") (pinfunction "2_2") (pintype "passive"))
      (node (ref "U5") (pin "23") (pinfunction "DAT2B0_23") (pintype "passive"))
    )
    (net (code "97") (name "/SD_DATA3") (class "Default")
      (node (ref "J3") (pin "2") (pinfunction "CD/DATA3/CS_2") (pintype "passive"))
      (node (ref "R10") (pin "2") (pinfunction "2_2") (pintype "passive"))
      (node (ref "U5") (pin "22") (pinfunction "DAT3B0_22") (pintype "passive"))
    )
    (net (code "98") (name "/SD_Det") (class "Default")
      (node (ref "J3") (pin "9") (pinfunction "Card-Detect_9") (pintype "passive"))
      (node (ref "R15") (pin "2") (pinfunction "2_2") (pintype "passive"))
      (node (ref "R35") (pin "1") (pinfunction "1_1") (pintype "passive"))
    )
    (net (code "99") (name "/USART1_RX") (class "Default")
      (node (ref "U4") (pin "B6") (pinfunction "IO_34_LN15_B6") (pintype "passive"))
      (node (ref "U7") (pin "2") (pinfunction "TXD_2") (pintype "passive"))
    )
    (net (code "100") (name "/USART1_TX") (class "Default")
      (node (ref "U4") (pin "B4") (pinfunction "IO_34_LP15_B4") (pintype "passive"))
      (node (ref "U7") (pin "3") (pinfunction "RXD_3") (pintype "passive"))
    )
    (net (code "101") (name "/USART3_RX") (class "Default")
      (node (ref "U10") (pin "1") (pinfunction "RO_1") (pintype "passive"))
      (node (ref "U4") (pin "A24") (pinfunction "IO_34_LP23_A24") (pintype "passive"))
    )
    (net (code "102") (name "/USART3_TX") (class "Default")
      (node (ref "U10") (pin "4") (pinfunction "DI_4") (pintype "passive"))
      (node (ref "U4") (pin "A18") (pinfunction "IO_35_L23P_A18") (pintype "passive"))
    )
    (net (code "103") (name "/USB_OTG_DM") (class "Default")
      (node (ref "U4") (pin "B61") (pinfunction "USB_OTG_DM_B61") (pintype "passive"))
      (node (ref "U6") (pin "6") (pinfunction "IO_6") (pintype "passive"))
      (node (ref "USB_OTG") (pin "2") (pinfunction "D-_2") (pintype "passive"))
    )
    (net (code "104") (name "/USB_OTG_DP") (class "Default")
      (node (ref "U4") (pin "B59") (pinfunction "USB_OTG_DP_B59") (pintype "passive"))
      (node (ref "U6") (pin "1") (pinfunction "IO_1") (pintype "passive"))
      (node (ref "USB_OTG") (pin "3") (pinfunction "D+_3") (pintype "passive"))
    )
    (net (code "105") (name "/USB_OTG_ID") (class "Default")
      (node (ref "U4") (pin "B65") (pinfunction "USB_OTG_ID_B65") (pintype "passive"))
      (node (ref "USB_OTG") (pin "4") (pinfunction "ID_4") (pintype "passive"))
      (node (ref "XS1") (pin "1") (pinfunction "1_1") (pintype "passive"))
    )
    (net (code "106") (name "/USB_OTG_VBUS") (class "Default")
      (node (ref "R4") (pin "1") (pinfunction "1_1") (pintype "passive"))
      (node (ref "U4") (pin "B63") (pinfunction "USB_VBUS_OTG_B63") (pintype "passive"))
      (node (ref "USB_OTG") (pin "1") (pinfunction "VCC_1") (pintype "passive"))
    )
    (net (code "107") (name "/V0_N") (class "Default")
      (node (ref "L4") (pin "1") (pinfunction "1_1") (pintype "passive"))
      (node (ref "U4") (pin "A76") (pinfunction "VN_0_A76") (pintype "passive"))
      (node (ref "XS2") (pin "2") (pinfunction "2_2") (pintype "passive"))
    )
    (net (code "108") (name "/V0_P") (class "Default")
      (node (ref "C21") (pin "2") (pinfunction "2_2") (pintype "passive"))
      (node (ref "C24") (pin "1") (pinfunction "1_1") (pintype "passive"))
      (node (ref "R14") (pin "2") (pinfunction "2_2") (pintype "passive"))
      (node (ref "R16") (pin "1") (pinfunction "1_1") (pintype "passive"))
      (node (ref "U4") (pin "A74") (pinfunction "VP_0_A74") (pintype "passive"))
      (node (ref "XS2") (pin "1") (pinfunction "1_1") (pintype "passive"))
    )
    (net (code "109") (name "/ZY_RST") (class "Default")
      (node (ref "U4") (pin "B110") (pinfunction "JTAG_~{RST}_B110") (pintype "passive"))
      (node (ref "XS5") (pin "14") (pinfunction "NC_14") (pintype "passive"))
    )
    (net (code "110") (name "/ZY_TCK") (class "Default")
      (node (ref "R22") (pin "1") (pinfunction "1_1") (pintype "passive"))
      (node (ref "U4") (pin "B112") (pinfunction "JTAG_TCK_B112") (pintype "passive"))
      (node (ref "XS5") (pin "6") (pinfunction "TCK_6") (pintype "passive"))
    )
    (net (code "111") (name "/ZY_TDI") (class "Default")
      (node (ref "R24") (pin "1") (pinfunction "1_1") (pintype "passive"))
      (node (ref "U4") (pin "B116") (pinfunction "JTAG_TDI_B116") (pintype "passive"))
      (node (ref "XS5") (pin "10") (pinfunction "TDI_10") (pintype "passive"))
    )
    (net (code "112") (name "/ZY_TDO") (class "Default")
      (node (ref "R23") (pin "1") (pinfunction "1_1") (pintype "passive"))
      (node (ref "U4") (pin "B118") (pinfunction "JTAG_TDO_B118") (pintype "passive"))
      (node (ref "XS5") (pin "8") (pinfunction "TDO_8") (pintype "passive"))
    )
    (net (code "113") (name "/ZY_TMS") (class "Default")
      (node (ref "R21") (pin "1") (pinfunction "1_1") (pintype "passive"))
      (node (ref "U4") (pin "B114") (pinfunction "JTAG_TMS_B114") (pintype "passive"))
      (node (ref "XS5") (pin "4") (pinfunction "TMS_4") (pintype "passive"))
    )
    (net (code "114") (name "AGND") (class "Default")
      (node (ref "C22") (pin "2") (pinfunction "2_2") (pintype "passive"))
      (node (ref "C23") (pin "2") (pinfunction "2_2") (pintype "passive"))
      (node (ref "C24") (pin "2") (pinfunction "2_2") (pintype "passive"))
      (node (ref "L3") (pin "2") (pinfunction "2_2") (pintype "passive"))
      (node (ref "L4") (pin "2") (pinfunction "2_2") (pintype "passive"))
      (node (ref "L5") (pin "2") (pinfunction "2_2") (pintype "passive"))
      (node (ref "R16") (pin "2") (pinfunction "2_2") (pintype "passive"))
      (node (ref "U4") (pin "A72") (pinfunction "AGND_A72") (pintype "passive"))
      (node (ref "U4") (pin "A78") (pinfunction "AGND_A78") (pintype "passive"))
      (node (ref "U4") (pin "A84") (pinfunction "AGND_A84") (pintype "passive"))
    )
    (net (code "115") (name "GND") (class "Default")
      (node (ref "C10") (pin "2") (pinfunction "2_2") (pintype "passive"))
      (node (ref "C11") (pin "1") (pinfunction "1_1") (pintype "passive"))
      (node (ref "C12") (pin "1") (pinfunction "1_1") (pintype "passive"))
      (node (ref "C13") (pin "2") (pinfunction "2_2") (pintype "passive"))
      (node (ref "C14") (pin "2") (pinfunction "2_2") (pintype "passive"))
      (node (ref "C15") (pin "2") (pinfunction "2_2") (pintype "passive"))
      (node (ref "C16") (pin "2") (pinfunction "2_2") (pintype "passive"))
      (node (ref "C17") (pin "2") (pinfunction "2_2") (pintype "passive"))
      (node (ref "C18") (pin "2") (pinfunction "2_2") (pintype "passive"))
      (node (ref "C19") (pin "1") (pinfunction "1_1") (pintype "passive"))
      (node (ref "C2") (pin "2") (pinfunction "2_2") (pintype "passive"))
      (node (ref "C20") (pin "1") (pinfunction "1_1") (pintype "passive"))
      (node (ref "C25") (pin "1") (pinfunction "1_1") (pintype "passive"))
      (node (ref "C26") (pin "2") (pinfunction "2_2") (pintype "passive"))
      (node (ref "C27") (pin "2") (pinfunction "2_2") (pintype "passive"))
      (node (ref "C28") (pin "1") (pinfunction "1_1") (pintype "passive"))
      (node (ref "C29") (pin "1") (pinfunction "1_1") (pintype "passive"))
      (node (ref "C3") (pin "2") (pinfunction "2_2") (pintype "passive"))
      (node (ref "C30") (pin "1") (pinfunction "1_1") (pintype "passive"))
      (node (ref "C31") (pin "2") (pinfunction "2_2") (pintype "passive"))
      (node (ref "C32") (pin "2") (pinfunction "2_2") (pintype "passive"))
      (node (ref "C33") (pin "2") (pinfunction "2_2") (pintype "passive"))
      (node (ref "C34") (pin "2") (pinfunction "2_2") (pintype "passive"))
      (node (ref "C4") (pin "2") (pinfunction "2_2") (pintype "passive"))
      (node (ref "C5") (pin "2") (pinfunction "2_2") (pintype "passive"))
      (node (ref "C6") (pin "2") (pinfunction "2_2") (pintype "passive"))
      (node (ref "C7") (pin "1") (pinfunction "1_1") (pintype "passive"))
      (node (ref "C8") (pin "1") (pinfunction "1_1") (pintype "passive"))
      (node (ref "C9") (pin "2") (pinfunction "2_2") (pintype "passive"))
      (node (ref "D2") (pin "1") (pinfunction "A_1") (pintype "passive"))
      (node (ref "DS1") (pin "2") (pinfunction "K_2") (pintype "passive"))
      (node (ref "DS3") (pin "2") (pinfunction "K_2") (pintype "passive"))
      (node (ref "H1") (pin "10") (pinfunction "GND_10") (pintype "passive"))
      (node (ref "H1") (pin "12") (pinfunction "LEDG-_12") (pintype "passive"))
      (node (ref "H1") (pin "13") (pinfunction "LEDY-_13") (pintype "passive"))
      (node (ref "H1") (pin "15") (pinfunction "GND_15") (pintype "passive"))
      (node (ref "H1") (pin "16") (pinfunction "GND_16") (pintype "passive"))
      (node (ref "J2") (pin "2") (pinfunction "2_2") (pintype "passive"))
      (node (ref "J2") (pin "3") (pinfunction "3_3") (pintype "passive"))
      (node (ref "J3") (pin "10") (pinfunction "10_10") (pintype "passive"))
      (node (ref "J3") (pin "11") (pinfunction "11_11") (pintype "passive"))
      (node (ref "J3") (pin "12") (pinfunction "12_12") (pintype "passive"))
      (node (ref "J3") (pin "13") (pinfunction "13_13") (pintype "passive"))
      (node (ref "J3") (pin "6") (pinfunction "VSS_6") (pintype "passive"))
      (node (ref "J7") (pin "3") (pinfunction "3_3") (pintype "passive"))
      (node (ref "JP1") (pin "2") (pinfunction "2_2") (pintype "passive"))
      (node (ref "JP1") (pin "5") (pinfunction "5_5") (pintype "passive"))
      (node (ref "JP1") (pin "6") (pinfunction "6_6") (pintype "passive"))
      (node (ref "L3") (pin "1") (pinfunction "1_1") (pintype "passive"))
      (node (ref "L5") (pin "1") (pinfunction "1_1") (pintype "passive"))
      (node (ref "Q1") (pin "2") (pinfunction "E_2") (pintype "passive"))
      (node (ref "R15") (pin "1") (pinfunction "1_1") (pintype "passive"))
      (node (ref "R2") (pin "2") (pinfunction "2_2") (pintype "passive"))
      (node (ref "R30") (pin "1") (pinfunction "1_1") (pintype "passive"))
      (node (ref "R34") (pin "2") (pinfunction "2_2") (pintype "passive"))
      (node (ref "R5") (pin "1") (pinfunction "1_1") (pintype "passive"))
      (node (ref "R6") (pin "2") (pinfunction "2_2") (pintype "passive"))
      (node (ref "R8") (pin "1") (pinfunction "1_1") (pintype "passive"))
      (node (ref "U1") (pin "6") (pinfunction "GND_6") (pintype "passive"))
      (node (ref "U1") (pin "9") (pinfunction "PowerPAD_9") (pintype "passive"))
      (node (ref "U10") (pin "5") (pinfunction "GND_5") (pintype "passive"))
      (node (ref "U2") (pin "3") (pinfunction "GND_3") (pintype "passive"))
      (node (ref "U2") (pin "6") (pinfunction "GND_6") (pintype "passive"))
      (node (ref "U3") (pin "1") (pinfunction "GND_1") (pintype "passive"))
      (node (ref "U4") (pin "A104") (pinfunction "GND_A104") (pintype "passive"))
      (node (ref "U4") (pin "A105") (pinfunction "GND_A105") (pintype "passive"))
      (node (ref "U4") (pin "A11") (pinfunction "GND_A11") (pintype "passive"))
      (node (ref "U4") (pin "A111") (pinfunction "GND_A111") (pintype "passive"))
      (node (ref "U4") (pin "A114") (pinfunction "GND_A114") (pintype "passive"))
      (node (ref "U4") (pin "A119") (pinfunction "GND_A119") (pintype "passive"))
      (node (ref "U4") (pin "A12") (pinfunction "GND_A12") (pintype "passive"))
      (node (ref "U4") (pin "A120") (pinfunction "GND_A120") (pintype "passive"))
      (node (ref "U4") (pin "A13") (pinfunction "GND_A13") (pintype "passive"))
      (node (ref "U4") (pin "A14") (pinfunction "GND_A14") (pintype "passive"))
      (node (ref "U4") (pin "A15") (pinfunction "GND_A15") (pintype "passive"))
      (node (ref "U4") (pin "A16") (pinfunction "GND_A16") (pintype "passive"))
      (node (ref "U4") (pin "A21") (pinfunction "GND_A21") (pintype "passive"))
      (node (ref "U4") (pin "A22") (pinfunction "GND_A22") (pintype "passive"))
      (node (ref "U4") (pin "A27") (pinfunction "GND_A27") (pintype "passive"))
      (node (ref "U4") (pin "A32") (pinfunction "GND_A32") (pintype "passive"))
      (node (ref "U4") (pin "A33") (pinfunction "GND_A33") (pintype "passive"))
      (node (ref "U4") (pin "A39") (pinfunction "GND_A39") (pintype "passive"))
      (node (ref "U4") (pin "A42") (pinfunction "GND_A42") (pintype "passive"))
      (node (ref "U4") (pin "A45") (pinfunction "GND_A45") (pintype "passive"))
      (node (ref "U4") (pin "A51") (pinfunction "GND_A51") (pintype "passive"))
      (node (ref "U4") (pin "A52") (pinfunction "GND_A52") (pintype "passive"))
      (node (ref "U4") (pin "A57") (pinfunction "GND_A57") (pintype "passive"))
      (node (ref "U4") (pin "A62") (pinfunction "GND_A62") (pintype "passive"))
      (node (ref "U4") (pin "A63") (pinfunction "GND_A63") (pintype "passive"))
      (node (ref "U4") (pin "A69") (pinfunction "GND_A69") (pintype "passive"))
      (node (ref "U4") (pin "A75") (pinfunction "GND_A75") (pintype "passive"))
      (node (ref "U4") (pin "A85") (pinfunction "GND_A85") (pintype "passive"))
      (node (ref "U4") (pin "A94") (pinfunction "GND_A94") (pintype "passive"))
      (node (ref "U4") (pin "A95") (pinfunction "GND_A95") (pintype "passive"))
      (node (ref "U4") (pin "B1") (pinfunction "GND_B1") (pintype "passive"))
      (node (ref "U4") (pin "B108") (pinfunction "GND_B108") (pintype "passive"))
      (node (ref "U4") (pin "B109") (pinfunction "GND_B109") (pintype "passive"))
      (node (ref "U4") (pin "B119") (pinfunction "GND_B119") (pintype "passive"))
      (node (ref "U4") (pin "B120") (pinfunction "GND_B120") (pintype "passive"))
      (node (ref "U4") (pin "B13") (pinfunction "GND_B13") (pintype "passive"))
      (node (ref "U4") (pin "B14") (pinfunction "GND_B14") (pintype "passive"))
      (node (ref "U4") (pin "B19") (pinfunction "GND_B19") (pintype "passive"))
      (node (ref "U4") (pin "B2") (pinfunction "GND_B2") (pintype "passive"))
      (node (ref "U4") (pin "B20") (pinfunction "GND_B20") (pintype "passive"))
      (node (ref "U4") (pin "B25") (pinfunction "GND_B25") (pintype "passive"))
      (node (ref "U4") (pin "B26") (pinfunction "GND_B26") (pintype "passive"))
      (node (ref "U4") (pin "B31") (pinfunction "GND_B31") (pintype "passive"))
      (node (ref "U4") (pin "B32") (pinfunction "GND_B32") (pintype "passive"))
      (node (ref "U4") (pin "B37") (pinfunction "GND_B37") (pintype "passive"))
      (node (ref "U4") (pin "B38") (pinfunction "GND_B38") (pintype "passive"))
      (node (ref "U4") (pin "B43") (pinfunction "GND_B43") (pintype "passive"))
      (node (ref "U4") (pin "B44") (pinfunction "GND_B44") (pintype "passive"))
      (node (ref "U4") (pin "B50") (pinfunction "GND_B50") (pintype "passive"))
      (node (ref "U4") (pin "B51") (pinfunction "GND_B51") (pintype "passive"))
      (node (ref "U4") (pin "B56") (pinfunction "GND_B56") (pintype "passive"))
      (node (ref "U4") (pin "B57") (pinfunction "GND_B57") (pintype "passive"))
      (node (ref "U4") (pin "B62") (pinfunction "GND_B62") (pintype "passive"))
      (node (ref "U4") (pin "B67") (pinfunction "GND_B67") (pintype "passive"))
      (node (ref "U4") (pin "B68") (pinfunction "GND_B68") (pintype "passive"))
      (node (ref "U4") (pin "B7") (pinfunction "GND_B7") (pintype "passive"))
      (node (ref "U4") (pin "B73") (pinfunction "GND_B73") (pintype "passive"))
      (node (ref "U4") (pin "B74") (pinfunction "AGND_B74") (pintype "passive"))
      (node (ref "U4") (pin "B79") (pinfunction "GND_B79") (pintype "passive"))
      (node (ref "U4") (pin "B8") (pinfunction "GND_B8") (pintype "passive"))
      (node (ref "U4") (pin "B84") (pinfunction "GND_B84") (pintype "passive"))
      (node (ref "U4") (pin "B89") (pinfunction "GND_B89") (pintype "passive"))
      (node (ref "U4") (pin "B94") (pinfunction "GND_B94") (pintype "passive"))
      (node (ref "U4") (pin "B99") (pinfunction "GND_B99") (pintype "passive"))
      (node (ref "U5") (pin "11") (pinfunction "GND_11") (pintype "passive"))
      (node (ref "U5") (pin "2") (pinfunction "GND_2") (pintype "passive"))
      (node (ref "U5") (pin "25") (pinfunction "EP_25") (pintype "passive"))
      (node (ref "U7") (pin "1") (pinfunction "GND_1") (pintype "passive"))
      (node (ref "U8") (pin "2") (pinfunction "VN_2") (pintype "passive"))
      (node (ref "U9") (pin "2") (pinfunction "GND_2") (pintype "passive"))
      (node (ref "USB1") (pin "4") (pinfunction "ID_4") (pintype "passive"))
      (node (ref "USB1") (pin "5") (pinfunction "GND_5") (pintype "passive"))
      (node (ref "USB1") (pin "6") (pintype "passive"))
      (node (ref "USB1") (pin "7") (pintype "passive"))
      (node (ref "USB1") (pin "8") (pintype "passive"))
      (node (ref "USB1") (pin "9") (pintype "passive"))
      (node (ref "USB_OTG") (pin "5") (pinfunction "GND_5") (pintype "passive"))
      (node (ref "USB_OTG") (pin "6") (pintype "passive"))
      (node (ref "USB_OTG") (pin "7") (pintype "passive"))
      (node (ref "USB_OTG") (pin "8") (pintype "passive"))
      (node (ref "USB_OTG") (pin "9") (pintype "passive"))
      (node (ref "XS5") (pin "1") (pinfunction "GND_1") (pintype "passive"))
      (node (ref "XS5") (pin "11") (pinfunction "GND_11") (pintype "passive"))
      (node (ref "XS5") (pin "13") (pinfunction "GND_13") (pintype "passive"))
      (node (ref "XS5") (pin "3") (pinfunction "GND_3") (pintype "passive"))
      (node (ref "XS5") (pin "5") (pinfunction "GND_5") (pintype "passive"))
      (node (ref "XS5") (pin "7") (pinfunction "GND_7") (pintype "passive"))
      (node (ref "XS5") (pin "9") (pinfunction "GND_9") (pintype "passive"))
    )
    (net (code "116") (name "Net-(C21-Pad1)") (class "Default")
      (node (ref "C21") (pin "1") (pinfunction "1_1") (pintype "passive"))
      (node (ref "C22") (pin "1") (pinfunction "1_1") (pintype "passive"))
      (node (ref "C23") (pin "1") (pinfunction "1_1") (pintype "passive"))
      (node (ref "L2") (pin "2") (pinfunction "2_2") (pintype "passive"))
      (node (ref "R14") (pin "1") (pinfunction "1_1") (pintype "passive"))
    )
    (net (code "117") (name "Net-(C34-Pad1)") (class "Default")
      (node (ref "C34") (pin "1") (pinfunction "1_1") (pintype "passive"))
      (node (ref "R27") (pin "2") (pinfunction "2_2") (pintype "passive"))
      (node (ref "R28") (pin "1") (pinfunction "1_1") (pintype "passive"))
    )
    (net (code "118") (name "Net-(D1-A)") (class "Default")
      (node (ref "C10") (pin "1") (pinfunction "1_1") (pintype "passive"))
      (node (ref "C13") (pin "1") (pinfunction "1_1") (pintype "passive"))
      (node (ref "C14") (pin "1") (pinfunction "1_1") (pintype "passive"))
      (node (ref "D1") (pin "1") (pinfunction "A_1") (pintype "passive"))
      (node (ref "L1") (pin "2") (pinfunction "2_2") (pintype "passive"))
      (node (ref "R1") (pin "1") (pinfunction "1_1") (pintype "passive"))
    )
    (net (code "119") (name "Net-(D2-K)") (class "Default")
      (node (ref "C1") (pin "2") (pinfunction "2_2") (pintype "passive"))
      (node (ref "D2") (pin "2") (pinfunction "K_2") (pintype "passive"))
      (node (ref "L1") (pin "1") (pinfunction "1_1") (pintype "passive"))
      (node (ref "U1") (pin "8") (pinfunction "PH_8") (pintype "passive"))
    )
    (net (code "120") (name "Net-(DS1-A)") (class "Default")
      (node (ref "DS1") (pin "1") (pinfunction "A_1") (pintype "passive"))
      (node (ref "R32") (pin "2") (pinfunction "2_2") (pintype "passive"))
    )
    (net (code "121") (name "Net-(DS2-A)") (class "Default")
      (node (ref "DS2") (pin "1") (pinfunction "A_1") (pintype "passive"))
      (node (ref "R3") (pin "2") (pinfunction "2_2") (pintype "passive"))
    )
    (net (code "122") (name "Net-(DS2-K)") (class "Default")
      (node (ref "DS2") (pin "2") (pinfunction "K_2") (pintype "passive"))
      (node (ref "Q1") (pin "3") (pinfunction "C_3") (pintype "passive"))
    )
    (net (code "123") (name "Net-(DS3-A)") (class "Default")
      (node (ref "DS3") (pin "1") (pinfunction "A_1") (pintype "passive"))
      (node (ref "R19") (pin "2") (pinfunction "2_2") (pintype "passive"))
    )
    (net (code "124") (name "Net-(H1-LEDG+)") (class "Default")
      (node (ref "H1") (pin "11") (pinfunction "LEDG+_11") (pintype "passive"))
      (node (ref "R17") (pin "2") (pinfunction "2_2") (pintype "passive"))
    )
    (net (code "125") (name "Net-(H1-LEDY+)") (class "Default")
      (node (ref "H1") (pin "14") (pinfunction "LEDY+_14") (pintype "passive"))
      (node (ref "R18") (pin "2") (pinfunction "2_2") (pintype "passive"))
    )
    (net (code "126") (name "Net-(H1-TCT)") (class "Default")
      (node (ref "C27") (pin "1") (pinfunction "1_1") (pintype "passive"))
      (node (ref "H1") (pin "1") (pinfunction "TCT_1") (pintype "passive"))
    )
    (net (code "127") (name "Net-(J1-Pad1)") (class "Default")
      (node (ref "J1") (pin "1") (pinfunction "1_1") (pintype "passive"))
      (node (ref "J2") (pin "1") (pinfunction "1_1") (pintype "passive"))
    )
    (net (code "128") (name "Net-(J7-Pad1)") (class "Default")
      (node (ref "J7") (pin "1") (pinfunction "1_1") (pintype "passive"))
      (node (ref "R37") (pin "2") (pinfunction "2_2") (pintype "passive"))
    )
    (net (code "129") (name "Net-(J7-Pad2)") (class "Default")
      (node (ref "J7") (pin "2") (pinfunction "2_2") (pintype "passive"))
      (node (ref "R36") (pin "2") (pinfunction "2_2") (pintype "passive"))
    )
    (net (code "130") (name "Net-(Q1-B)") (class "Default")
      (node (ref "Q1") (pin "1") (pinfunction "B_1") (pintype "passive"))
      (node (ref "R4") (pin "2") (pinfunction "2_2") (pintype "passive"))
      (node (ref "R6") (pin "1") (pinfunction "1_1") (pintype "passive"))
    )
    (net (code "131") (name "Net-(R5-Pad2)") (class "Default")
      (node (ref "R5") (pin "2") (pinfunction "2_2") (pintype "passive"))
      (node (ref "XS1") (pin "2") (pinfunction "2_2") (pintype "passive"))
    )
    (net (code "132") (name "Net-(U1-BOOT)") (class "Default")
      (node (ref "C1") (pin "1") (pinfunction "1_1") (pintype "passive"))
      (node (ref "U1") (pin "1") (pinfunction "BOOT_1") (pintype "passive"))
    )
    (net (code "133") (name "Net-(U1-VSENSE)") (class "Default")
      (node (ref "R1") (pin "2") (pinfunction "2_2") (pintype "passive"))
      (node (ref "R2") (pin "1") (pinfunction "1_1") (pintype "passive"))
      (node (ref "U1") (pin "4") (pinfunction "VSENSE_4") (pintype "passive"))
    )
    (net (code "134") (name "Net-(U2-OUT)") (class "Default")
      (node (ref "C11") (pin "2") (pinfunction "2_2") (pintype "passive"))
      (node (ref "C4") (pin "1") (pinfunction "1_1") (pintype "passive"))
      (node (ref "L8") (pin "1") (pinfunction "1_1") (pintype "passive"))
      (node (ref "L9") (pin "1") (pinfunction "1_1") (pintype "passive"))
      (node (ref "R33") (pin "1") (pinfunction "1_1") (pintype "passive"))
      (node (ref "U2") (pin "4") (pinfunction "OUT_4") (pintype "passive"))
    )
    (net (code "135") (name "Net-(U2-SENSE{slash}ADJ)") (class "Default")
      (node (ref "R33") (pin "2") (pinfunction "2_2") (pintype "passive"))
      (node (ref "R34") (pin "1") (pinfunction "1_1") (pintype "passive"))
      (node (ref "U2") (pin "5") (pinfunction "SENSE/ADJ_5") (pintype "passive"))
    )
    (net (code "136") (name "Net-(U4B-SPI1_CS_3V3)") (class "Default")
      (node (ref "R35") (pin "2") (pinfunction "2_2") (pintype "passive"))
      (node (ref "U4") (pin "B103") (pinfunction "SPI1_CS_3V3_B103") (pintype "passive"))
    )
    (net (code "137") (name "Net-(U5-SEL)") (class "Default")
      (node (ref "R7") (pin "2") (pinfunction "2_2") (pintype "passive"))
      (node (ref "R8") (pin "2") (pinfunction "2_2") (pintype "passive"))
      (node (ref "U5") (pin "24") (pinfunction "SEL_24") (pintype "passive"))
    )
    (net (code "138") (name "Net-(U7-UD+)") (class "Default")
      (node (ref "U7") (pin "5") (pinfunction "UD+_5") (pintype "passive"))
      (node (ref "U8") (pin "1") (pinfunction "IO_1") (pintype "passive"))
      (node (ref "USB1") (pin "3") (pinfunction "D+_3") (pintype "passive"))
    )
    (net (code "139") (name "Net-(U7-UD-)") (class "Default")
      (node (ref "U7") (pin "6") (pinfunction "UD-_6") (pintype "passive"))
      (node (ref "U8") (pin "6") (pinfunction "IO_6") (pintype "passive"))
      (node (ref "USB1") (pin "2") (pinfunction "D-_2") (pintype "passive"))
    )
    (net (code "140") (name "Net-(U7-V3)") (class "Default")
      (node (ref "C25") (pin "2") (pinfunction "2_2") (pintype "passive"))
      (node (ref "U7") (pin "4") (pinfunction "V3_4") (pintype "passive"))
    )
    (net (code "141") (name "Net-(U7-XI)") (class "Default")
      (node (ref "C28") (pin "2") (pinfunction "2_2") (pintype "passive"))
      (node (ref "U7") (pin "7") (pinfunction "XI_7") (pintype "passive"))
      (node (ref "Y1") (pin "1") (pinfunction "OSC1_1") (pintype "passive"))
    )
    (net (code "142") (name "Net-(U7-XO)") (class "Default")
      (node (ref "C29") (pin "2") (pinfunction "2_2") (pintype "passive"))
      (node (ref "U7") (pin "8") (pinfunction "XO_8") (pintype "passive"))
      (node (ref "Y1") (pin "2") (pinfunction "OSC3_2") (pintype "passive"))
    )
    (net (code "143") (name "Net-(U9-RS{slash}NC)") (class "Default")
      (node (ref "R30") (pin "2") (pinfunction "2_2") (pintype "passive"))
      (node (ref "U9") (pin "8") (pinfunction "RS/NC_8") (pintype "passive"))
    )
    (net (code "144") (name "Net-(U9-RXD)") (class "Default")
      (node (ref "R31") (pin "2") (pinfunction "2_2") (pintype "passive"))
      (node (ref "U9") (pin "4") (pinfunction "RXD_4") (pintype "passive"))
    )
    (net (code "145") (name "Net-(U9-TXD)") (class "Default")
      (node (ref "R29") (pin "2") (pinfunction "2_2") (pintype "passive"))
      (node (ref "U9") (pin "1") (pinfunction "TXD_1") (pintype "passive"))
    )
    (net (code "146") (name "Net-(U9-VCC)") (class "Default")
      (node (ref "C31") (pin "1") (pinfunction "1_1") (pintype "passive"))
      (node (ref "C32") (pin "1") (pinfunction "1_1") (pintype "passive"))
      (node (ref "L7") (pin "2") (pinfunction "2_2") (pintype "passive"))
      (node (ref "U9") (pin "3") (pinfunction "VCC_3") (pintype "passive"))
    )
    (net (code "147") (name "Net-(U10-VCC)") (class "Default")
      (node (ref "C33") (pin "1") (pinfunction "1_1") (pintype "passive"))
      (node (ref "L6") (pin "1") (pinfunction "1_1") (pintype "passive"))
      (node (ref "R25") (pin "2") (pinfunction "2_2") (pintype "passive"))
      (node (ref "U10") (pin "8") (pinfunction "VCC_8") (pintype "passive"))
    )
    (net (code "148") (name "Net-(USB1-VCC)") (class "Default")
      (node (ref "USB1") (pin "1") (pinfunction "VCC_1") (pintype "passive"))
      (node (ref "XS4") (pin "1") (pinfunction "1_1") (pintype "passive"))
    )
    (net (code "149") (name "VCC5V") (class "Default")
      (node (ref "C15") (pin "1") (pinfunction "1_1") (pintype "passive"))
      (node (ref "C16") (pin "1") (pinfunction "1_1") (pintype "passive"))
      (node (ref "C17") (pin "1") (pinfunction "1_1") (pintype "passive"))
      (node (ref "C18") (pin "1") (pinfunction "1_1") (pintype "passive"))
      (node (ref "C26") (pin "1") (pinfunction "1_1") (pintype "passive"))
      (node (ref "C30") (pin "2") (pinfunction "2_2") (pintype "passive"))
      (node (ref "C5") (pin "1") (pinfunction "1_1") (pintype "passive"))
      (node (ref "C6") (pin "1") (pinfunction "1_1") (pintype "passive"))
      (node (ref "D1") (pin "2") (pinfunction "K_2") (pintype "passive"))
      (node (ref "JP1") (pin "3") (pinfunction "3_3") (pintype "passive"))
      (node (ref "JP1") (pin "4") (pinfunction "4_4") (pintype "passive"))
      (node (ref "R32") (pin "1") (pinfunction "1_1") (pintype "passive"))
      (node (ref "U2") (pin "1") (pinfunction "~{SHDN}_1") (pintype "passive"))
      (node (ref "U2") (pin "2") (pinfunction "IN_2") (pintype "passive"))
      (node (ref "U4") (pin "A1") (pinfunction "VCC_5V_A1") (pintype "passive"))
      (node (ref "U4") (pin "A10") (pinfunction "VCC_5V_A10") (pintype "passive"))
      (node (ref "U4") (pin "A2") (pinfunction "VCC_5V_A2") (pintype "passive"))
      (node (ref "U4") (pin "A3") (pinfunction "VCC_5V_A3") (pintype "passive"))
      (node (ref "U4") (pin "A4") (pinfunction "VCC_5V_A4") (pintype "passive"))
      (node (ref "U4") (pin "A5") (pinfunction "VCC_5V_A5") (pintype "passive"))
      (node (ref "U4") (pin "A6") (pinfunction "VCC_5V_A6") (pintype "passive"))
      (node (ref "U4") (pin "A7") (pinfunction "VCC_5V_A7") (pintype "passive"))
      (node (ref "U4") (pin "A8") (pinfunction "VCC_5V_A8") (pintype "passive"))
      (node (ref "U4") (pin "A9") (pinfunction "VCC_5V_A9") (pintype "passive"))
      (node (ref "U7") (pin "16") (pinfunction "VCC_16") (pintype "passive"))
      (node (ref "U8") (pin "5") (pinfunction "VP_5") (pintype "passive"))
      (node (ref "XS4") (pin "2") (pinfunction "2_2") (pintype "passive"))
    )
    (net (code "150") (name "VCC12V") (class "Default")
      (node (ref "C2") (pin "1") (pinfunction "1_1") (pintype "passive"))
      (node (ref "C3") (pin "1") (pinfunction "1_1") (pintype "passive"))
      (node (ref "J1") (pin "2") (pinfunction "2_2") (pintype "passive"))
      (node (ref "U1") (pin "7") (pinfunction "VIN_7") (pintype "passive"))
    )
    (net (code "151") (name "VDD1V8") (class "Default")
      (node (ref "C12") (pin "2") (pinfunction "2_2") (pintype "passive"))
      (node (ref "C19") (pin "2") (pinfunction "2_2") (pintype "passive"))
      (node (ref "C9") (pin "1") (pinfunction "1_1") (pintype "passive"))
      (node (ref "L2") (pin "1") (pinfunction "1_1") (pintype "passive"))
      (node (ref "R7") (pin "1") (pinfunction "1_1") (pintype "passive"))
      (node (ref "U3") (pin "2") (pinfunction "VOUT_2") (pintype "passive"))
      (node (ref "U3") (pin "4") (pinfunction "VOUT_4") (pintype "passive"))
      (node (ref "U5") (pin "5") (pinfunction "VCCA_5") (pintype "passive"))
    )
    (net (code "152") (name "VDD3V3") (class "Default")
      (node (ref "C20") (pin "2") (pinfunction "2_2") (pintype "passive"))
      (node (ref "C7") (pin "2") (pinfunction "2_2") (pintype "passive"))
      (node (ref "C8") (pin "2") (pinfunction "2_2") (pintype "passive"))
      (node (ref "J3") (pin "4") (pinfunction "VDD_4") (pintype "passive"))
      (node (ref "JP1") (pin "1") (pinfunction "1_1") (pintype "passive"))
      (node (ref "L6") (pin "2") (pinfunction "2_2") (pintype "passive"))
      (node (ref "L7") (pin "1") (pinfunction "1_1") (pintype "passive"))
      (node (ref "L8") (pin "2") (pinfunction "2_2") (pintype "passive"))
      (node (ref "L9") (pin "2") (pinfunction "2_2") (pintype "passive"))
      (node (ref "R10") (pin "1") (pinfunction "1_1") (pintype "passive"))
      (node (ref "R11") (pin "1") (pinfunction "1_1") (pintype "passive"))
      (node (ref "R12") (pin "1") (pinfunction "1_1") (pintype "passive"))
      (node (ref "R13") (pin "1") (pinfunction "1_1") (pintype "passive"))
      (node (ref "R20") (pin "2") (pinfunction "2_2") (pintype "passive"))
      (node (ref "R21") (pin "2") (pinfunction "2_2") (pintype "passive"))
      (node (ref "R22") (pin "2") (pinfunction "2_2") (pintype "passive"))
      (node (ref "R23") (pin "2") (pinfunction "2_2") (pintype "passive"))
      (node (ref "R24") (pin "2") (pinfunction "2_2") (pintype "passive"))
      (node (ref "R3") (pin "1") (pinfunction "1_1") (pintype "passive"))
      (node (ref "R9") (pin "1") (pinfunction "1_1") (pintype "passive"))
      (node (ref "U3") (pin "3") (pinfunction "VIN_3") (pintype "passive"))
      (node (ref "U5") (pin "17") (pinfunction "VCCB1_17") (pintype "passive"))
      (node (ref "U5") (pin "21") (pinfunction "VCCB0_21") (pintype "passive"))
    )
    (net (code "153") (name "unconnected-(U1-ENA-Pad5)") (class "Default")
      (node (ref "U1") (pin "5") (pinfunction "ENA_5") (pintype "passive+no_connect"))
    )
    (net (code "154") (name "unconnected-(U1-NC-Pad2)") (class "Default")
      (node (ref "U1") (pin "2") (pinfunction "NC_2") (pintype "passive+no_connect"))
    )
    (net (code "155") (name "unconnected-(U1-NC-Pad3)") (class "Default")
      (node (ref "U1") (pin "3") (pinfunction "NC_3") (pintype "passive+no_connect"))
    )
    (net (code "156") (name "unconnected-(U4A-IO_13_6-PadA117)") (class "Default")
      (node (ref "U4") (pin "A117") (pinfunction "IO_13_6_A117") (pintype "passive"))
    )
    (net (code "157") (name "unconnected-(U4A-IO_13_LN16-PadA99)") (class "Default")
      (node (ref "U4") (pin "A99") (pinfunction "IO_13_LN16_A99") (pintype "passive"))
    )
    (net (code "158") (name "unconnected-(U4A-IO_13_LN21-PadA89)") (class "Default")
      (node (ref "U4") (pin "A89") (pinfunction "IO_13_LN21_A89") (pintype "passive"))
    )
    (net (code "159") (name "unconnected-(U4A-IO_13_LP16-PadA97)") (class "Default")
      (node (ref "U4") (pin "A97") (pinfunction "IO_13_LP16_A97") (pintype "passive"))
    )
    (net (code "160") (name "unconnected-(U4A-IO_13_LP21-PadA87)") (class "Default")
      (node (ref "U4") (pin "A87") (pinfunction "IO_13_LP21_A87") (pintype "passive"))
    )
    (net (code "161") (name "unconnected-(U4A-IO_34_L4N-PadA71)") (class "Default")
      (node (ref "U4") (pin "A71") (pinfunction "IO_34_L4N_A71") (pintype "passive"))
    )
    (net (code "162") (name "unconnected-(U4A-IO_34_L4P-PadA73)") (class "Default")
      (node (ref "U4") (pin "A73") (pinfunction "IO_34_L4P_A73") (pintype "passive"))
    )
    (net (code "163") (name "unconnected-(U4A-IO_34_L17N-PadA41)") (class "Default")
      (node (ref "U4") (pin "A41") (pinfunction "IO_34_L17N_A41") (pintype "passive"))
    )
    (net (code "164") (name "unconnected-(U4A-IO_34_L17P-PadA43)") (class "Default")
      (node (ref "U4") (pin "A43") (pinfunction "IO_34_L17P_A43") (pintype "passive"))
    )
    (net (code "165") (name "unconnected-(U4A-IO_34_L22N-PadA47)") (class "Default")
      (node (ref "U4") (pin "A47") (pinfunction "IO_34_L22N_A47") (pintype "passive"))
    )
    (net (code "166") (name "unconnected-(U4A-IO_34_L22P-PadA49)") (class "Default")
      (node (ref "U4") (pin "A49") (pinfunction "IO_34_L22P_A49") (pintype "passive"))
    )
    (net (code "167") (name "unconnected-(U4A-IO_34_LN3-PadA86)") (class "Default")
      (node (ref "U4") (pin "A86") (pinfunction "IO_34_LN3_A86") (pintype "passive"))
    )
    (net (code "168") (name "unconnected-(U4A-IO_34_LN18-PadA61)") (class "Default")
      (node (ref "U4") (pin "A61") (pinfunction "IO_34_LN18_A61") (pintype "passive"))
    )
    (net (code "169") (name "unconnected-(U4A-IO_34_LN20-PadA83)") (class "Default")
      (node (ref "U4") (pin "A83") (pinfunction "IO_34_LN20_A83") (pintype "passive"))
    )
    (net (code "170") (name "unconnected-(U4A-IO_34_LN23-PadA26)") (class "Default")
      (node (ref "U4") (pin "A26") (pinfunction "IO_34_LN23_A26") (pintype "passive"))
    )
    (net (code "171") (name "unconnected-(U4A-IO_34_LP3-PadA88)") (class "Default")
      (node (ref "U4") (pin "A88") (pinfunction "IO_34_LP3_A88") (pintype "passive"))
    )
    (net (code "172") (name "unconnected-(U4A-IO_34_LP18-PadA59)") (class "Default")
      (node (ref "U4") (pin "A59") (pinfunction "IO_34_LP18_A59") (pintype "passive"))
    )
    (net (code "173") (name "unconnected-(U4A-IO_34_LP20-PadA81)") (class "Default")
      (node (ref "U4") (pin "A81") (pinfunction "IO_34_LP20_A81") (pintype "passive"))
    )
    (net (code "174") (name "unconnected-(U4B-FPGA_VBATT-PadB115)") (class "Default")
      (node (ref "U4") (pin "B115") (pinfunction "FPGA_VBATT_B115") (pintype "passive"))
    )
    (net (code "175") (name "unconnected-(U4B-IO_34_LN13-PadB3)") (class "Default")
      (node (ref "U4") (pin "B3") (pinfunction "IO_34_LN13_B3") (pintype "passive"))
    )
    (net (code "176") (name "unconnected-(U4B-IO_34_LN14-PadB10)") (class "Default")
      (node (ref "U4") (pin "B10") (pinfunction "IO_34_LN14_B10") (pintype "passive"))
    )
    (net (code "177") (name "unconnected-(U4B-IO_34_LP13-PadB5)") (class "Default")
      (node (ref "U4") (pin "B5") (pinfunction "IO_34_LP13_B5") (pintype "passive"))
    )
    (net (code "178") (name "unconnected-(U4B-IO_34_LP14-PadB12)") (class "Default")
      (node (ref "U4") (pin "B12") (pinfunction "IO_34_LP14_B12") (pintype "passive"))
    )
    (net (code "179") (name "unconnected-(U4B-IO_35_0-PadB95)") (class "Default")
      (node (ref "U4") (pin "B95") (pinfunction "IO_35_0_B95") (pintype "passive"))
    )
    (net (code "180") (name "unconnected-(U4B-IO_35_25-PadB97)") (class "Default")
      (node (ref "U4") (pin "B97") (pinfunction "IO_35_25_B97") (pintype "passive"))
    )
    (net (code "181") (name "unconnected-(U4B-IO_35_LN1-PadB80)") (class "Default")
      (node (ref "U4") (pin "B80") (pinfunction "IO_35_LN1_B80") (pintype "passive"))
    )
    (net (code "182") (name "unconnected-(U4B-IO_35_LN4-PadB78)") (class "Default")
      (node (ref "U4") (pin "B78") (pinfunction "IO_35_LN4_B78") (pintype "passive"))
    )
    (net (code "183") (name "unconnected-(U4B-IO_35_LN6-PadB71)") (class "Default")
      (node (ref "U4") (pin "B71") (pinfunction "IO_35_LN6_B71") (pintype "passive"))
    )
    (net (code "184") (name "unconnected-(U4B-IO_35_LN7-PadB16)") (class "Default")
      (node (ref "U4") (pin "B16") (pinfunction "IO_35_LN7_B16") (pintype "passive"))
    )
    (net (code "185") (name "unconnected-(U4B-IO_35_LN8-PadB11)") (class "Default")
      (node (ref "U4") (pin "B11") (pinfunction "IO_35_LN8_B11") (pintype "passive"))
    )
    (net (code "186") (name "unconnected-(U4B-IO_35_LN9-PadB15)") (class "Default")
      (node (ref "U4") (pin "B15") (pinfunction "IO_35_LN9_B15") (pintype "passive"))
    )
    (net (code "187") (name "unconnected-(U4B-IO_35_LN10-PadB36)") (class "Default")
      (node (ref "U4") (pin "B36") (pinfunction "IO_35_LN10_B36") (pintype "passive"))
    )
    (net (code "188") (name "unconnected-(U4B-IO_35_LN11-PadB22)") (class "Default")
      (node (ref "U4") (pin "B22") (pinfunction "IO_35_LN11_B22") (pintype "passive"))
    )
    (net (code "189") (name "unconnected-(U4B-IO_35_LN12-PadB66)") (class "Default")
      (node (ref "U4") (pin "B66") (pinfunction "IO_35_LN12_B66") (pintype "passive"))
    )
    (net (code "190") (name "unconnected-(U4B-IO_35_LN13-PadB90)") (class "Default")
      (node (ref "U4") (pin "B90") (pinfunction "IO_35_LN13_B90") (pintype "passive"))
    )
    (net (code "191") (name "unconnected-(U4B-IO_35_LN14-PadB72)") (class "Default")
      (node (ref "U4") (pin "B72") (pinfunction "IO_35_LN14_B72") (pintype "passive"))
    )
    (net (code "192") (name "unconnected-(U4B-IO_35_LN15-PadB52)") (class "Default")
      (node (ref "U4") (pin "B52") (pinfunction "IO_35_LN15_B52") (pintype "passive"))
    )
    (net (code "193") (name "unconnected-(U4B-IO_35_LN17-PadB28)") (class "Default")
      (node (ref "U4") (pin "B28") (pinfunction "IO_35_LN17_B28") (pintype "passive"))
    )
    (net (code "194") (name "unconnected-(U4B-IO_35_LN18-PadB42)") (class "Default")
      (node (ref "U4") (pin "B42") (pinfunction "IO_35_LN18_B42") (pintype "passive"))
    )
    (net (code "195") (name "unconnected-(U4B-IO_35_LN24-PadB88)") (class "Default")
      (node (ref "U4") (pin "B88") (pinfunction "IO_35_LN24_B88") (pintype "passive"))
    )
    (net (code "196") (name "unconnected-(U4B-IO_35_LP1-PadB82)") (class "Default")
      (node (ref "U4") (pin "B82") (pinfunction "IO_35_LP1_B82") (pintype "passive"))
    )
    (net (code "197") (name "unconnected-(U4B-IO_35_LP2-PadB81)") (class "Default")
      (node (ref "U4") (pin "B81") (pinfunction "IO_35_LP2_B81") (pintype "passive"))
    )
    (net (code "198") (name "unconnected-(U4B-IO_35_LP4-PadB76)") (class "Default")
      (node (ref "U4") (pin "B76") (pinfunction "IO_35_LP4_B76") (pintype "passive"))
    )
    (net (code "199") (name "unconnected-(U4B-IO_35_LP5-PadB46)") (class "Default")
      (node (ref "U4") (pin "B46") (pinfunction "IO_35_LP5_B46") (pintype "passive"))
    )
    (net (code "200") (name "unconnected-(U4B-IO_35_LP6-PadB69)") (class "Default")
      (node (ref "U4") (pin "B69") (pinfunction "IO_35_LP6_B69") (pintype "passive"))
    )
    (net (code "201") (name "unconnected-(U4B-IO_35_LP7-PadB18)") (class "Default")
      (node (ref "U4") (pin "B18") (pinfunction "IO_35_LP7_B18") (pintype "passive"))
    )
    (net (code "202") (name "unconnected-(U4B-IO_35_LP8-PadB9)") (class "Default")
      (node (ref "U4") (pin "B9") (pinfunction "IO_35_LP8_B9") (pintype "passive"))
    )
    (net (code "203") (name "unconnected-(U4B-IO_35_LP9-PadB17)") (class "Default")
      (node (ref "U4") (pin "B17") (pinfunction "IO_35_LP9_B17") (pintype "passive"))
    )
    (net (code "204") (name "unconnected-(U4B-IO_35_LP10-PadB34)") (class "Default")
      (node (ref "U4") (pin "B34") (pinfunction "IO_35_LP10_B34") (pintype "passive"))
    )
    (net (code "205") (name "unconnected-(U4B-IO_35_LP11-PadB24)") (class "Default")
      (node (ref "U4") (pin "B24") (pinfunction "IO_35_LP11_B24") (pintype "passive"))
    )
    (net (code "206") (name "unconnected-(U4B-IO_35_LP12-PadB64)") (class "Default")
      (node (ref "U4") (pin "B64") (pinfunction "IO_35_LP12_B64") (pintype "passive"))
    )
    (net (code "207") (name "unconnected-(U4B-IO_35_LP13-PadB92)") (class "Default")
      (node (ref "U4") (pin "B92") (pinfunction "IO_35_LP13_B92") (pintype "passive"))
    )
    (net (code "208") (name "unconnected-(U4B-IO_35_LP14-PadB70)") (class "Default")
      (node (ref "U4") (pin "B70") (pinfunction "IO_35_LP14_B70") (pintype "passive"))
    )
    (net (code "209") (name "unconnected-(U4B-IO_35_LP15-PadB54)") (class "Default")
      (node (ref "U4") (pin "B54") (pinfunction "IO_35_LP15_B54") (pintype "passive"))
    )
    (net (code "210") (name "unconnected-(U4B-IO_35_LP17-PadB30)") (class "Default")
      (node (ref "U4") (pin "B30") (pinfunction "IO_35_LP17_B30") (pintype "passive"))
    )
    (net (code "211") (name "unconnected-(U4B-IO_35_LP18-PadB40)") (class "Default")
      (node (ref "U4") (pin "B40") (pinfunction "IO_35_LP18_B40") (pintype "passive"))
    )
    (net (code "212") (name "unconnected-(U4B-IO_35_LP20-PadB93)") (class "Default")
      (node (ref "U4") (pin "B93") (pinfunction "IO_35_LP20_B93") (pintype "passive"))
    )
    (net (code "213") (name "unconnected-(U4B-IO_35_LP22-PadB60)") (class "Default")
      (node (ref "U4") (pin "B60") (pinfunction "IO_35_LP22_B60") (pintype "passive"))
    )
    (net (code "214") (name "unconnected-(U4B-IO_35_LP24-PadB86)") (class "Default")
      (node (ref "U4") (pin "B86") (pinfunction "IO_35_LP24_B86") (pintype "passive"))
    )
    (net (code "215") (name "unconnected-(U4B-SPI1_SCLK_3V3-PadB101)") (class "Default")
      (node (ref "U4") (pin "B101") (pinfunction "SPI1_SCLK_3V3_B101") (pintype "passive"))
    )
    (net (code "216") (name "unconnected-(U5-CLKB1-Pad13)") (class "Default")
      (node (ref "U5") (pin "13") (pinfunction "CLKB1_13") (pintype "passive"))
    )
    (net (code "217") (name "unconnected-(U5-CMDB1-Pad12)") (class "Default")
      (node (ref "U5") (pin "12") (pinfunction "CMDB1_12") (pintype "passive"))
    )
    (net (code "218") (name "unconnected-(U5-DAT0B1-Pad14)") (class "Default")
      (node (ref "U5") (pin "14") (pinfunction "DAT0B1_14") (pintype "passive"))
    )
    (net (code "219") (name "unconnected-(U5-DAT1B1-Pad15)") (class "Default")
      (node (ref "U5") (pin "15") (pinfunction "DAT1B1_15") (pintype "passive"))
    )
    (net (code "220") (name "unconnected-(U5-DAT2B1-Pad8)") (class "Default")
      (node (ref "U5") (pin "8") (pinfunction "DAT2B1_8") (pintype "passive"))
    )
    (net (code "221") (name "unconnected-(U5-DAT3B1-Pad10)") (class "Default")
      (node (ref "U5") (pin "10") (pinfunction "DAT3B1_10") (pintype "passive"))
    )
    (net (code "222") (name "unconnected-(U6-IO-Pad3)") (class "Default")
      (node (ref "U6") (pin "3") (pinfunction "IO_3") (pintype "passive"))
    )
    (net (code "223") (name "unconnected-(U6-IO-Pad4)") (class "Default")
      (node (ref "U6") (pin "4") (pinfunction "IO_4") (pintype "passive"))
    )
    (net (code "224") (name "unconnected-(U6-VN-Pad2)") (class "Default")
      (node (ref "U6") (pin "2") (pinfunction "VN_2") (pintype "passive"))
    )
    (net (code "225") (name "unconnected-(U6-VP-Pad5)") (class "Default")
      (node (ref "U6") (pin "5") (pinfunction "VP_5") (pintype "passive"))
    )
    (net (code "226") (name "unconnected-(U7-CTS#-Pad9)") (class "Default")
      (node (ref "U7") (pin "9") (pinfunction "CTS#_9") (pintype "passive"))
    )
    (net (code "227") (name "unconnected-(U7-DCD#-Pad12)") (class "Default")
      (node (ref "U7") (pin "12") (pinfunction "DCD#_12") (pintype "passive"))
    )
    (net (code "228") (name "unconnected-(U7-DSR#-Pad10)") (class "Default")
      (node (ref "U7") (pin "10") (pinfunction "DSR#_10") (pintype "passive"))
    )
    (net (code "229") (name "unconnected-(U7-DTR#-Pad13)") (class "Default")
      (node (ref "U7") (pin "13") (pinfunction "DTR#_13") (pintype "passive"))
    )
    (net (code "230") (name "unconnected-(U7-R232-Pad15)") (class "Default")
      (node (ref "U7") (pin "15") (pinfunction "R232_15") (pintype "passive"))
    )
    (net (code "231") (name "unconnected-(U7-RI-Pad11)") (class "Default")
      (node (ref "U7") (pin "11") (pinfunction "RI_11") (pintype "passive"))
    )
    (net (code "232") (name "unconnected-(U7-RTS#-Pad14)") (class "Default")
      (node (ref "U7") (pin "14") (pinfunction "RTS#_14") (pintype "passive"))
    )
    (net (code "233") (name "unconnected-(U8-IO-Pad3)") (class "Default")
      (node (ref "U8") (pin "3") (pinfunction "IO_3") (pintype "passive"))
    )
    (net (code "234") (name "unconnected-(U8-IO-Pad4)") (class "Default")
      (node (ref "U8") (pin "4") (pinfunction "IO_4") (pintype "passive"))
    )
    (net (code "235") (name "unconnected-(U9-Vref{slash}NC-Pad5)") (class "Default")
      (node (ref "U9") (pin "5") (pinfunction "Vref/NC_5") (pintype "passive"))
    )
    (net (code "236") (name "unconnected-(XS5-NC-Pad12)") (class "Default")
      (node (ref "XS5") (pin "12") (pinfunction "NC_12") (pintype "passive+no_connect"))
    )
  )
)
